# BMS_Slave_v2_1.net
KiCad netlist of a schematic drawn in EAGLE
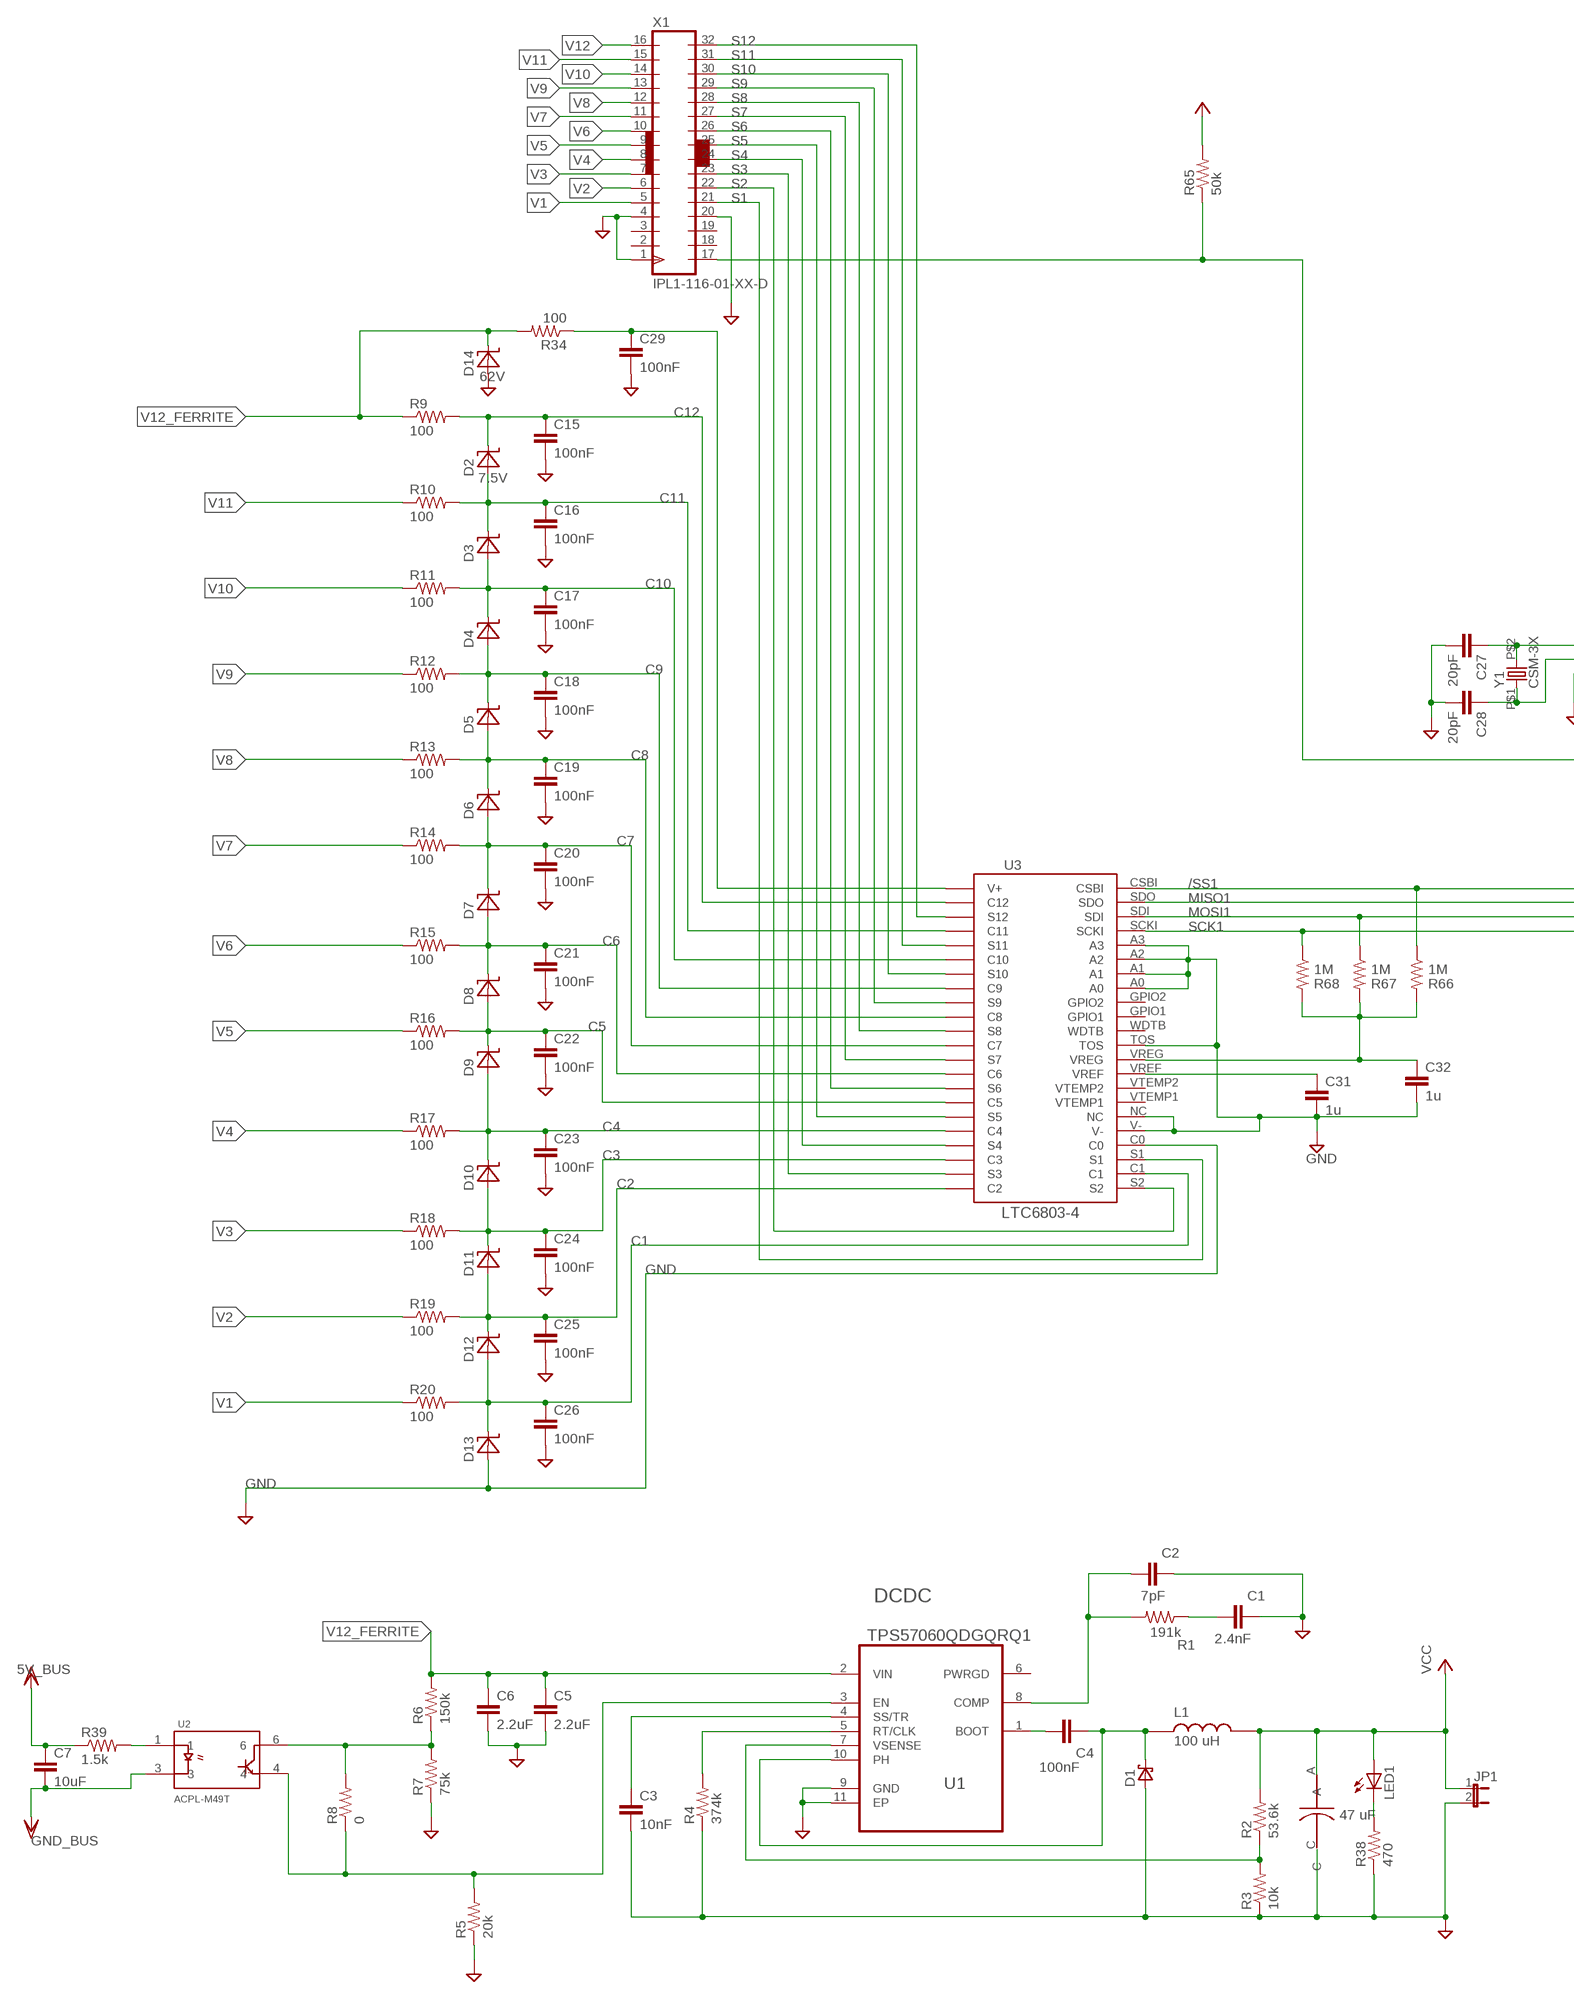
[diagram p0: schematic, sheet 1, part 1 of 2]
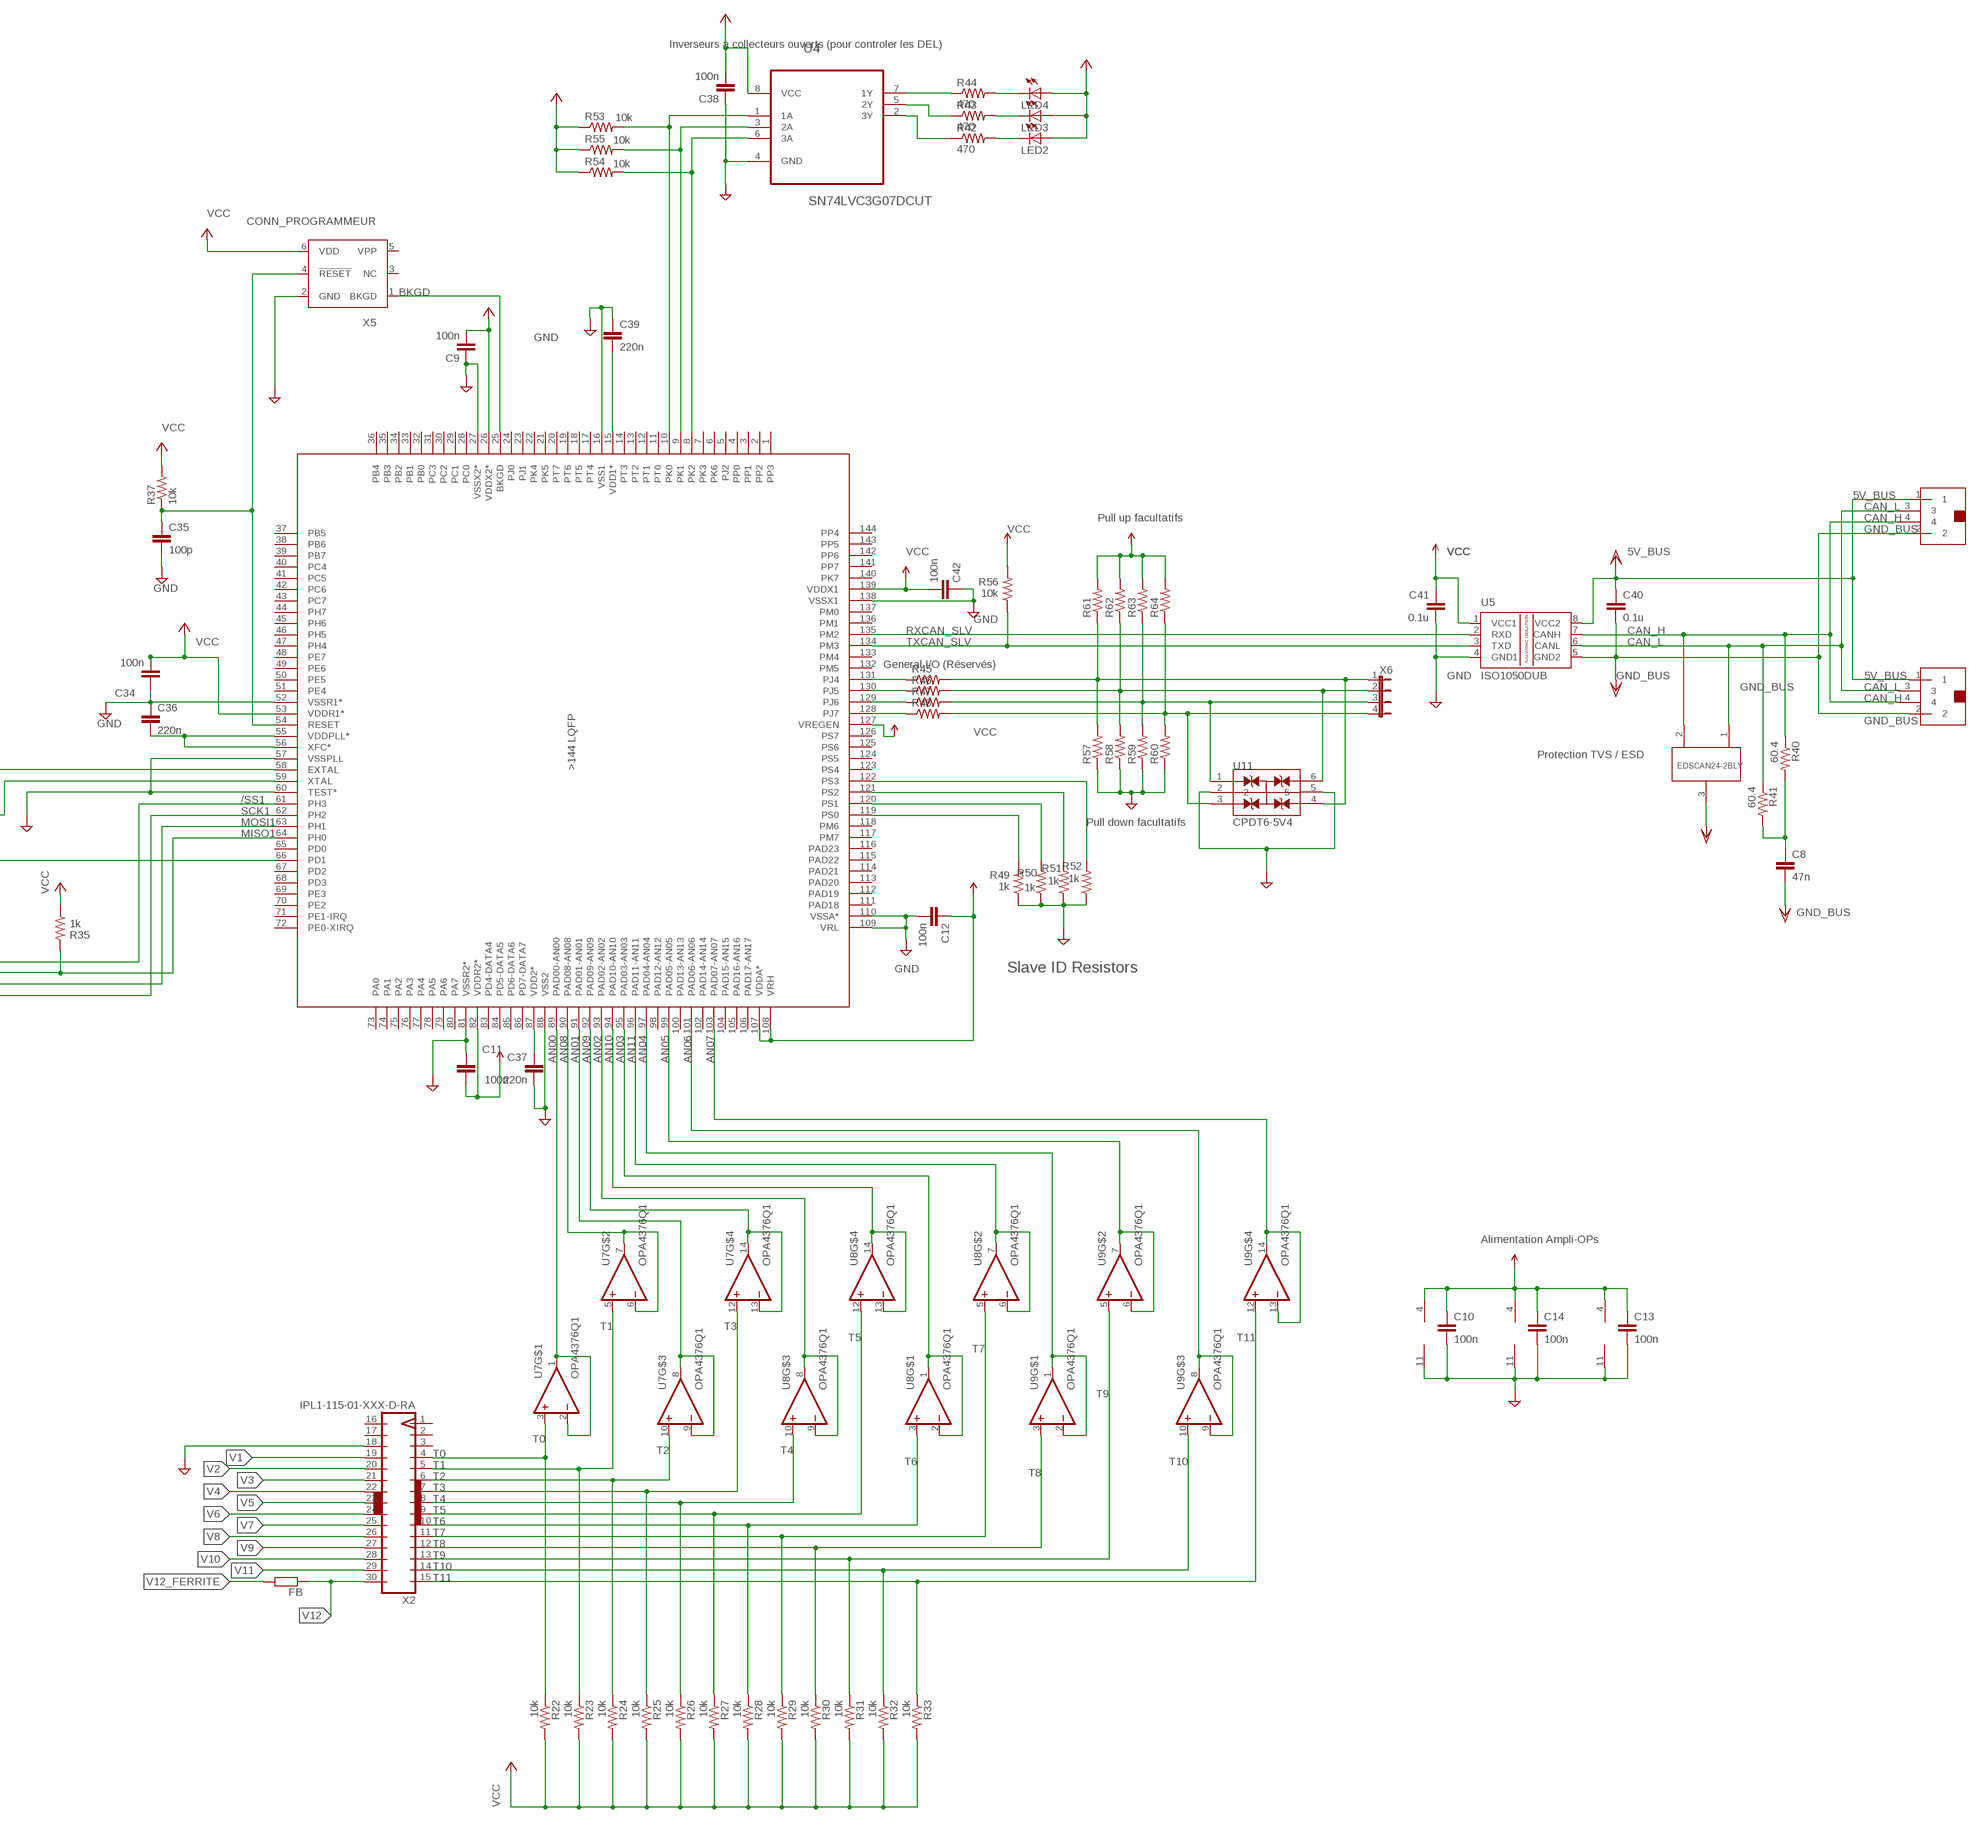
[diagram p1: schematic, sheet 1, part 2 of 2]

(export (version "E")
  (design (tool "Eeschema 10.0.6"))
  (components
    (comp (ref "C1")
      (value "2.4nF")
      (footprint "eagle-import:C0603")
      (libsource (lib "eagle-import") (part "CC0603"))
    )
    (comp (ref "C2")
      (value "7pF")
      (footprint "eagle-import:C0603")
      (libsource (lib "eagle-import") (part "CC0603"))
    )
    (comp (ref "C3")
      (value "10nF")
      (footprint "eagle-import:C0603")
      (libsource (lib "eagle-import") (part "CC0603"))
    )
    (comp (ref "C4")
      (value "100nF")
      (footprint "eagle-import:C0603")
      (libsource (lib "eagle-import") (part "CC0603"))
    )
    (comp (ref "C5")
      (value "2.2uF")
      (footprint "eagle-import:C3225")
      (libsource (lib "eagle-import") (part "resistor_C-EUC3225"))
    )
    (comp (ref "C6")
      (value "2.2uF")
      (footprint "eagle-import:C3225")
      (libsource (lib "eagle-import") (part "resistor_C-EUC3225"))
    )
    (comp (ref "C7")
      (value "10uF")
      (footprint "eagle-import:C0603")
      (libsource (lib "eagle-import") (part "CC0603"))
    )
    (comp (ref "C8")
      (value "47n")
      (footprint "eagle-import:C0603")
      (libsource (lib "eagle-import") (part "C-EUC0603"))
    )
    (comp (ref "C9")
      (value "100n")
      (footprint "eagle-import:C0603")
      (libsource (lib "eagle-import") (part "C-EUC0603"))
    )
    (comp (ref "C10")
      (value "100n")
      (footprint "eagle-import:C0603")
      (libsource (lib "eagle-import") (part "C-EUC0603"))
    )
    (comp (ref "C11")
      (value "100n")
      (footprint "eagle-import:C0603")
      (libsource (lib "eagle-import") (part "CC0603"))
    )
    (comp (ref "C12")
      (value "100n")
      (footprint "eagle-import:C0603")
      (libsource (lib "eagle-import") (part "C-EUC0603"))
    )
    (comp (ref "C13")
      (value "100n")
      (footprint "eagle-import:C0603")
      (libsource (lib "eagle-import") (part "C-EUC0603"))
    )
    (comp (ref "C14")
      (value "100n")
      (footprint "eagle-import:C0603")
      (libsource (lib "eagle-import") (part "C-EUC0603"))
    )
    (comp (ref "C15")
      (value "100nF")
      (footprint "eagle-import:C0603")
      (libsource (lib "eagle-import") (part "CC0603"))
    )
    (comp (ref "C16")
      (value "100nF")
      (footprint "eagle-import:C0603")
      (libsource (lib "eagle-import") (part "CC0603"))
    )
    (comp (ref "C17")
      (value "100nF")
      (footprint "eagle-import:C0603")
      (libsource (lib "eagle-import") (part "CC0603"))
    )
    (comp (ref "C18")
      (value "100nF")
      (footprint "eagle-import:C0603")
      (libsource (lib "eagle-import") (part "CC0603"))
    )
    (comp (ref "C19")
      (value "100nF")
      (footprint "eagle-import:C0603")
      (libsource (lib "eagle-import") (part "CC0603"))
    )
    (comp (ref "C20")
      (value "100nF")
      (footprint "eagle-import:C0603")
      (libsource (lib "eagle-import") (part "CC0603"))
    )
    (comp (ref "C21")
      (value "100nF")
      (footprint "eagle-import:C0603")
      (libsource (lib "eagle-import") (part "CC0603"))
    )
    (comp (ref "C22")
      (value "100nF")
      (footprint "eagle-import:C0603")
      (libsource (lib "eagle-import") (part "CC0603"))
    )
    (comp (ref "C23")
      (value "100nF")
      (footprint "eagle-import:C0603")
      (libsource (lib "eagle-import") (part "CC0603"))
    )
    (comp (ref "C24")
      (value "100nF")
      (footprint "eagle-import:C0603")
      (libsource (lib "eagle-import") (part "CC0603"))
    )
    (comp (ref "C25")
      (value "100nF")
      (footprint "eagle-import:C0603")
      (libsource (lib "eagle-import") (part "CC0603"))
    )
    (comp (ref "C26")
      (value "100nF")
      (footprint "eagle-import:C0603")
      (libsource (lib "eagle-import") (part "CC0603"))
    )
    (comp (ref "C27")
      (value "20pF")
      (footprint "eagle-import:C0603")
      (libsource (lib "eagle-import") (part "C-EUC0603"))
    )
    (comp (ref "C28")
      (value "20pF")
      (footprint "eagle-import:C0603")
      (libsource (lib "eagle-import") (part "C-EUC0603"))
    )
    (comp (ref "C29")
      (value "100nF")
      (footprint "eagle-import:C0603")
      (libsource (lib "eagle-import") (part "CC0603"))
    )
    (comp (ref "C31")
      (value "1u")
      (footprint "eagle-import:C0603")
      (libsource (lib "eagle-import") (part "CC0603"))
    )
    (comp (ref "C32")
      (value "1u")
      (footprint "eagle-import:C0603")
      (libsource (lib "eagle-import") (part "CC0603"))
    )
    (comp (ref "C34")
      (value "100n")
      (footprint "eagle-import:C0603")
      (libsource (lib "eagle-import") (part "CC0603"))
    )
    (comp (ref "C35")
      (value "100p")
      (footprint "eagle-import:C0603")
      (libsource (lib "eagle-import") (part "CC0603"))
    )
    (comp (ref "C36")
      (value "220n")
      (footprint "eagle-import:C0603")
      (libsource (lib "eagle-import") (part "CC0603"))
    )
    (comp (ref "C37")
      (value "220n")
      (footprint "eagle-import:C0603")
      (libsource (lib "eagle-import") (part "C-EUC0603"))
    )
    (comp (ref "C38")
      (value "100n")
      (footprint "eagle-import:C0603")
      (libsource (lib "eagle-import") (part "C-EUC0603"))
    )
    (comp (ref "C39")
      (value "220n")
      (footprint "eagle-import:C0603")
      (libsource (lib "eagle-import") (part "C-EUC0603"))
    )
    (comp (ref "C40")
      (value "0.1u")
      (footprint "eagle-import:C0603")
      (libsource (lib "eagle-import") (part "C-EUC0603"))
    )
    (comp (ref "C41")
      (value "0.1u")
      (footprint "eagle-import:C0603")
      (libsource (lib "eagle-import") (part "C-EUC0603"))
    )
    (comp (ref "C42")
      (value "100n")
      (footprint "eagle-import:C0603")
      (libsource (lib "eagle-import") (part "C-EUC0603"))
    )
    (comp (ref "C43")
      (value "47 uF")
      (footprint "eagle-import:APXE_CONDENSATEUR")
      (libsource (lib "eagle-import") (part "APXE_47_COND"))
    )
    (comp (ref "D1")
      (value "BYS12-90GENERIC")
      (footprint "eagle-import:DO214AC_ZENER")
      (libsource (lib "eagle-import") (part "BYS12-90GENERIC"))
    )
    (comp (ref "D2")
      (value "DIODE_ZENER")
      (footprint "eagle-import:SOD123")
      (libsource (lib "eagle-import") (part "DIODE_ZENER"))
    )
    (comp (ref "D3")
      (value "DIODE_ZENER")
      (footprint "eagle-import:SOD123")
      (libsource (lib "eagle-import") (part "DIODE_ZENER"))
    )
    (comp (ref "D4")
      (value "DIODE_ZENER")
      (footprint "eagle-import:SOD123")
      (libsource (lib "eagle-import") (part "DIODE_ZENER"))
    )
    (comp (ref "D5")
      (value "DIODE_ZENER")
      (footprint "eagle-import:SOD123")
      (libsource (lib "eagle-import") (part "DIODE_ZENER"))
    )
    (comp (ref "D6")
      (value "DIODE_ZENER")
      (footprint "eagle-import:SOD123")
      (libsource (lib "eagle-import") (part "DIODE_ZENER"))
    )
    (comp (ref "D7")
      (value "DIODE_ZENER")
      (footprint "eagle-import:SOD123")
      (libsource (lib "eagle-import") (part "DIODE_ZENER"))
    )
    (comp (ref "D8")
      (value "DIODE_ZENER")
      (footprint "eagle-import:SOD123")
      (libsource (lib "eagle-import") (part "DIODE_ZENER"))
    )
    (comp (ref "D9")
      (value "DIODE_ZENER")
      (footprint "eagle-import:SOD123")
      (libsource (lib "eagle-import") (part "DIODE_ZENER"))
    )
    (comp (ref "D10")
      (value "DIODE_ZENER")
      (footprint "eagle-import:SOD123")
      (libsource (lib "eagle-import") (part "DIODE_ZENER"))
    )
    (comp (ref "D11")
      (value "DIODE_ZENER")
      (footprint "eagle-import:SOD123")
      (libsource (lib "eagle-import") (part "DIODE_ZENER"))
    )
    (comp (ref "D12")
      (value "DIODE_ZENER")
      (footprint "eagle-import:SOD123")
      (libsource (lib "eagle-import") (part "DIODE_ZENER"))
    )
    (comp (ref "D13")
      (value "DIODE_ZENER")
      (footprint "eagle-import:SOD123")
      (libsource (lib "eagle-import") (part "DIODE_ZENER"))
    )
    (comp (ref "D14")
      (value "DIODE_ZENER")
      (footprint "eagle-import:SOD123")
      (libsource (lib "eagle-import") (part "DIODE_ZENER"))
    )
    (comp (ref "FB")
      (value "R-EU_R0805")
      (footprint "eagle-import:R0805")
      (libsource (lib "eagle-import") (part "R-EU_R0805"))
    )
    (comp (ref "JP1")
      (value "JP1E")
      (footprint "eagle-import:JP1")
      (libsource (lib "eagle-import") (part "JP1E"))
    )
    (comp (ref "L1")
      (value "100 uH")
      (footprint "eagle-import:VLP8040T-101M")
      (libsource (lib "eagle-import") (part "VLP8040T-101M"))
    )
    (comp (ref "LED1")
      (value "LED")
      (footprint "eagle-import:1206_LED")
      (libsource (lib "eagle-import") (part "LED"))
    )
    (comp (ref "LED2")
      (value "LED")
      (footprint "eagle-import:1206_LED")
      (libsource (lib "eagle-import") (part "ELE4000_BMS_LED"))
    )
    (comp (ref "LED3")
      (value "LED")
      (footprint "eagle-import:1206_LED")
      (libsource (lib "eagle-import") (part "ELE4000_BMS_LED"))
    )
    (comp (ref "LED4")
      (value "LED")
      (footprint "eagle-import:1206_LED")
      (libsource (lib "eagle-import") (part "ELE4000_BMS_LED"))
    )
    (comp (ref "R1")
      (value "191k")
      (footprint "eagle-import:R0603")
      (libsource (lib "eagle-import") (part "resistor_R-US_R0603"))
    )
    (comp (ref "R2")
      (value "53.6k")
      (footprint "eagle-import:R0603")
      (libsource (lib "eagle-import") (part "resistor_R-US_R0603"))
    )
    (comp (ref "R3")
      (value "10k")
      (footprint "eagle-import:R0603")
      (libsource (lib "eagle-import") (part "resistor_R-US_R0603"))
    )
    (comp (ref "R4")
      (value "374k")
      (footprint "eagle-import:R0603")
      (libsource (lib "eagle-import") (part "resistor_R-US_R0603"))
    )
    (comp (ref "R5")
      (value "20k")
      (footprint "eagle-import:R0603")
      (libsource (lib "eagle-import") (part "resistor_R-US_R0603"))
    )
    (comp (ref "R6")
      (value "150k")
      (footprint "eagle-import:R0603")
      (libsource (lib "eagle-import") (part "resistor_R-US_R0603"))
    )
    (comp (ref "R7")
      (value "75k")
      (footprint "eagle-import:R0603")
      (libsource (lib "eagle-import") (part "resistor_R-US_R0603"))
    )
    (comp (ref "R8")
      (value "0")
      (footprint "eagle-import:R0603")
      (libsource (lib "eagle-import") (part "resistor_R-US_R0603"))
    )
    (comp (ref "R9")
      (value "100")
      (footprint "eagle-import:R0603")
      (libsource (lib "eagle-import") (part "resistor_R-US_R0603"))
    )
    (comp (ref "R10")
      (value "100")
      (footprint "eagle-import:R0603")
      (libsource (lib "eagle-import") (part "resistor_R-US_R0603"))
    )
    (comp (ref "R11")
      (value "100")
      (footprint "eagle-import:R0603")
      (libsource (lib "eagle-import") (part "resistor_R-US_R0603"))
    )
    (comp (ref "R12")
      (value "100")
      (footprint "eagle-import:R0603")
      (libsource (lib "eagle-import") (part "resistor_R-US_R0603"))
    )
    (comp (ref "R13")
      (value "100")
      (footprint "eagle-import:R0603")
      (libsource (lib "eagle-import") (part "resistor_R-US_R0603"))
    )
    (comp (ref "R14")
      (value "100")
      (footprint "eagle-import:R0603")
      (libsource (lib "eagle-import") (part "resistor_R-US_R0603"))
    )
    (comp (ref "R15")
      (value "100")
      (footprint "eagle-import:R0603")
      (libsource (lib "eagle-import") (part "resistor_R-US_R0603"))
    )
    (comp (ref "R16")
      (value "100")
      (footprint "eagle-import:R0603")
      (libsource (lib "eagle-import") (part "resistor_R-US_R0603"))
    )
    (comp (ref "R17")
      (value "100")
      (footprint "eagle-import:R0603")
      (libsource (lib "eagle-import") (part "resistor_R-US_R0603"))
    )
    (comp (ref "R18")
      (value "100")
      (footprint "eagle-import:R0603")
      (libsource (lib "eagle-import") (part "resistor_R-US_R0603"))
    )
    (comp (ref "R19")
      (value "100")
      (footprint "eagle-import:R0603")
      (libsource (lib "eagle-import") (part "resistor_R-US_R0603"))
    )
    (comp (ref "R20")
      (value "100")
      (footprint "eagle-import:R0603")
      (libsource (lib "eagle-import") (part "resistor_R-US_R0603"))
    )
    (comp (ref "R22")
      (value "10k")
      (footprint "eagle-import:R0603")
      (libsource (lib "eagle-import") (part "R-US_R0603"))
    )
    (comp (ref "R23")
      (value "10k")
      (footprint "eagle-import:R0603")
      (libsource (lib "eagle-import") (part "R-US_R0603"))
    )
    (comp (ref "R24")
      (value "10k")
      (footprint "eagle-import:R0603")
      (libsource (lib "eagle-import") (part "R-US_R0603"))
    )
    (comp (ref "R25")
      (value "10k")
      (footprint "eagle-import:R0603")
      (libsource (lib "eagle-import") (part "R-US_R0603"))
    )
    (comp (ref "R26")
      (value "10k")
      (footprint "eagle-import:R0603")
      (libsource (lib "eagle-import") (part "R-US_R0603"))
    )
    (comp (ref "R27")
      (value "10k")
      (footprint "eagle-import:R0603")
      (libsource (lib "eagle-import") (part "R-US_R0603"))
    )
    (comp (ref "R28")
      (value "10k")
      (footprint "eagle-import:R0603")
      (libsource (lib "eagle-import") (part "R-US_R0603"))
    )
    (comp (ref "R29")
      (value "10k")
      (footprint "eagle-import:R0603")
      (libsource (lib "eagle-import") (part "R-US_R0603"))
    )
    (comp (ref "R30")
      (value "10k")
      (footprint "eagle-import:R0603")
      (libsource (lib "eagle-import") (part "R-US_R0603"))
    )
    (comp (ref "R31")
      (value "10k")
      (footprint "eagle-import:R0603")
      (libsource (lib "eagle-import") (part "R-US_R0603"))
    )
    (comp (ref "R32")
      (value "10k")
      (footprint "eagle-import:R0603")
      (libsource (lib "eagle-import") (part "R-US_R0603"))
    )
    (comp (ref "R33")
      (value "10k")
      (footprint "eagle-import:R0603")
      (libsource (lib "eagle-import") (part "R-US_R0603"))
    )
    (comp (ref "R34")
      (value "100")
      (footprint "eagle-import:R0603")
      (libsource (lib "eagle-import") (part "resistor_R-US_R0603"))
    )
    (comp (ref "R35")
      (value "1k")
      (footprint "eagle-import:R0603")
      (libsource (lib "eagle-import") (part "resistor_R-US_R0603"))
    )
    (comp (ref "R37")
      (value "10k")
      (footprint "eagle-import:R0603")
      (libsource (lib "eagle-import") (part "resistor_R-US_R0603"))
    )
    (comp (ref "R38")
      (value "470")
      (footprint "eagle-import:R0603")
      (libsource (lib "eagle-import") (part "R-US_R0603"))
    )
    (comp (ref "R39")
      (value "1.5k")
      (footprint "eagle-import:R0603")
      (libsource (lib "eagle-import") (part "resistor_R-US_R0603"))
    )
    (comp (ref "R40")
      (value "60.4")
      (footprint "eagle-import:R0603")
      (libsource (lib "eagle-import") (part "R-US_R0603"))
    )
    (comp (ref "R41")
      (value "60.4")
      (footprint "eagle-import:R0603")
      (libsource (lib "eagle-import") (part "R-US_R0603"))
    )
    (comp (ref "R42")
      (value "470")
      (footprint "eagle-import:R0603")
      (libsource (lib "eagle-import") (part "resistor_R-US_R0603"))
    )
    (comp (ref "R43")
      (value "470")
      (footprint "eagle-import:R0603")
      (libsource (lib "eagle-import") (part "resistor_R-US_R0603"))
    )
    (comp (ref "R44")
      (value "470")
      (footprint "eagle-import:R0603")
      (libsource (lib "eagle-import") (part "resistor_R-US_R0603"))
    )
    (comp (ref "R45")
      (value "R-US_R0603")
      (footprint "eagle-import:R0603")
      (libsource (lib "eagle-import") (part "R-US_R0603"))
    )
    (comp (ref "R46")
      (value "R-US_R0603")
      (footprint "eagle-import:R0603")
      (libsource (lib "eagle-import") (part "R-US_R0603"))
    )
    (comp (ref "R47")
      (value "R-US_R0603")
      (footprint "eagle-import:R0603")
      (libsource (lib "eagle-import") (part "R-US_R0603"))
    )
    (comp (ref "R48")
      (value "R-US_R0603")
      (footprint "eagle-import:R0603")
      (libsource (lib "eagle-import") (part "R-US_R0603"))
    )
    (comp (ref "R49")
      (value "1k")
      (footprint "eagle-import:R0603")
      (libsource (lib "eagle-import") (part "resistor_R-US_R0603"))
    )
    (comp (ref "R50")
      (value "1k")
      (footprint "eagle-import:R0603")
      (libsource (lib "eagle-import") (part "resistor_R-US_R0603"))
    )
    (comp (ref "R51")
      (value "1k")
      (footprint "eagle-import:R0603")
      (libsource (lib "eagle-import") (part "resistor_R-US_R0603"))
    )
    (comp (ref "R52")
      (value "1k")
      (footprint "eagle-import:R0603")
      (libsource (lib "eagle-import") (part "resistor_R-US_R0603"))
    )
    (comp (ref "R53")
      (value "10k")
      (footprint "eagle-import:R0603")
      (libsource (lib "eagle-import") (part "resistor_R-US_R0603"))
    )
    (comp (ref "R54")
      (value "10k")
      (footprint "eagle-import:R0603")
      (libsource (lib "eagle-import") (part "resistor_R-US_R0603"))
    )
    (comp (ref "R55")
      (value "10k")
      (footprint "eagle-import:R0603")
      (libsource (lib "eagle-import") (part "resistor_R-US_R0603"))
    )
    (comp (ref "R56")
      (value "10k")
      (footprint "eagle-import:R0603")
      (libsource (lib "eagle-import") (part "resistor_R-US_R0603"))
    )
    (comp (ref "R57")
      (value "R-US_R0603")
      (footprint "eagle-import:R0603")
      (libsource (lib "eagle-import") (part "R-US_R0603"))
    )
    (comp (ref "R58")
      (value "R-US_R0603")
      (footprint "eagle-import:R0603")
      (libsource (lib "eagle-import") (part "R-US_R0603"))
    )
    (comp (ref "R59")
      (value "R-US_R0603")
      (footprint "eagle-import:R0603")
      (libsource (lib "eagle-import") (part "R-US_R0603"))
    )
    (comp (ref "R60")
      (value "R-US_R0603")
      (footprint "eagle-import:R0603")
      (libsource (lib "eagle-import") (part "R-US_R0603"))
    )
    (comp (ref "R61")
      (value "R-US_R0603")
      (footprint "eagle-import:R0603")
      (libsource (lib "eagle-import") (part "R-US_R0603"))
    )
    (comp (ref "R62")
      (value "R-US_R0603")
      (footprint "eagle-import:R0603")
      (libsource (lib "eagle-import") (part "R-US_R0603"))
    )
    (comp (ref "R63")
      (value "R-US_R0603")
      (footprint "eagle-import:R0603")
      (libsource (lib "eagle-import") (part "R-US_R0603"))
    )
    (comp (ref "R64")
      (value "R-US_R0603")
      (footprint "eagle-import:R0603")
      (libsource (lib "eagle-import") (part "R-US_R0603"))
    )
    (comp (ref "R65")
      (value "50k")
      (footprint "eagle-import:R0603")
      (libsource (lib "eagle-import") (part "resistor_R-US_R0603"))
    )
    (comp (ref "R66")
      (value "1M")
      (footprint "eagle-import:R0603")
      (libsource (lib "eagle-import") (part "resistor_R-US_R0603"))
    )
    (comp (ref "R67")
      (value "1M")
      (footprint "eagle-import:R0603")
      (libsource (lib "eagle-import") (part "resistor_R-US_R0603"))
    )
    (comp (ref "R68")
      (value "1M")
      (footprint "eagle-import:R0603")
      (libsource (lib "eagle-import") (part "resistor_R-US_R0603"))
    )
    (comp (ref "U1")
      (value "TPS57060QDGQRQ1")
      (footprint "eagle-import:SOP50P490X110-11N")
      (fields (field (name "MPN") "TPS54060QDGQRQ1"))
      (libsource (lib "eagle-import") (part "TPS54060QDGQRQ1"))
    )
    (comp (ref "U2")
      (value "ACPL-M49T")
      (footprint "eagle-import:SO5")
      (libsource (lib "eagle-import") (part "ACPL-M49T"))
    )
    (comp (ref "U3")
      (value "LTC6803-4")
      (footprint "eagle-import:LTC6803-4")
      (libsource (lib "eagle-import") (part "LTC6803-4"))
    )
    (comp (ref "U4")
      (value "SN74LVC3G07DCUT")
      (footprint "eagle-import:SOP50P310X90-8N")
      (libsource (lib "eagle-import") (part "SN74LVC3G07DCUT"))
    )
    (comp (ref "U5")
      (value "ISO1050DUB")
      (footprint "eagle-import:DUB-R-PDSO-G8")
      (fields (field (name "MPN") "ISO1050DUBR"))
      (libsource (lib "eagle-import") (part "ISO1050DUB"))
    )
    (comp (ref "U6")
      (value "MC9S12XD-144")
      (footprint "eagle-import:SQFP-S-20X20-144")
      (fields (field (name "MPN") "LFDAS12XFLT"))
      (libsource (lib "eagle-import") (part "MC9S12XD-144"))
    )
    (comp (ref "U7")
      (value "OPA4376Q1")
      (footprint "eagle-import:TSSOP-14")
      (libsource (lib "eagle-import") (part "OPA4376Q1"))
    )
    (comp (ref "U8")
      (value "OPA4376Q1")
      (footprint "eagle-import:TSSOP-14")
      (libsource (lib "eagle-import") (part "OPA4376Q1"))
    )
    (comp (ref "U9")
      (value "OPA4376Q1")
      (footprint "eagle-import:TSSOP-14")
      (libsource (lib "eagle-import") (part "OPA4376Q1"))
    )
    (comp (ref "U10")
      (value "EDSCAN24-2BLY")
      (footprint "eagle-import:SOT23-3")
      (libsource (lib "eagle-import") (part "EDSCAN24-2BLY"))
    )
    (comp (ref "U11")
      (value "CPDT6-5V4")
      (footprint "eagle-import:SOT23-6")
      (libsource (lib "eagle-import") (part "CPDT6-5V4"))
    )
    (comp (ref "X1")
      (value "IPL1-116-01-XX-D")
      (footprint "eagle-import:IPL1-116-01-XX-D")
      (libsource (lib "eagle-import") (part "IPL1-116-01-XX-D"))
    )
    (comp (ref "X2")
      (value "IPL1-115-01-XXX-D-RA")
      (footprint "eagle-import:IPL1-115-01-XXX-D-RA")
      (libsource (lib "eagle-import") (part "IPL1-115-01-XXX-D-RA"))
    )
    (comp (ref "X3")
      (value "IPL1-102-01-XXX-D-RA")
      (footprint "eagle-import:IPL1-102-01-XXX-D-RA")
      (libsource (lib "eagle-import") (part "IPL1-102-01-XXX-D-RA"))
    )
    (comp (ref "X4")
      (value "IPL1-102-01-XXX-D-RA")
      (footprint "eagle-import:IPL1-102-01-XXX-D-RA")
      (libsource (lib "eagle-import") (part "IPL1-102-01-XXX-D-RA"))
    )
    (comp (ref "X5")
      (value "CONN_PROGRAMMEUR")
      (footprint "eagle-import:CONNECTEUR_PROGRAMMEUR")
      (libsource (lib "eagle-import") (part "CONN_PROGRAMMEUR"))
    )
    (comp (ref "X6")
      (value "JP4E")
      (footprint "eagle-import:JP4")
      (libsource (lib "eagle-import") (part "JP4E"))
    )
    (comp (ref "Y1")
      (value "CSM-3X")
      (footprint "eagle-import:CSM-3X")
      (libsource (lib "eagle-import") (part "CSM-3X"))
    )
  )
  (nets
    (net (code "1") (name "/AN00") (class "Default")
      (node (ref "U6") (pin "89") (pinfunction "PAD00-AN00_89") (pintype "bidirectional"))
      (node (ref "U7") (pin "1") (pinfunction "OUT_1") (pintype "output"))
      (node (ref "U7") (pin "2") (pinfunction "-IN_2") (pintype "input"))
    )
    (net (code "2") (name "/AN01") (class "Default")
      (node (ref "U6") (pin "91") (pinfunction "PAD01-AN01_91") (pintype "bidirectional"))
      (node (ref "U7") (pin "8") (pinfunction "OUT_8") (pintype "output"))
      (node (ref "U7") (pin "9") (pinfunction "-IN_9") (pintype "input"))
    )
    (net (code "3") (name "/AN02") (class "Default")
      (node (ref "U6") (pin "93") (pinfunction "PAD02-AN02_93") (pintype "bidirectional"))
      (node (ref "U8") (pin "8") (pinfunction "OUT_8") (pintype "output"))
      (node (ref "U8") (pin "9") (pinfunction "-IN_9") (pintype "input"))
    )
    (net (code "4") (name "/AN03") (class "Default")
      (node (ref "U6") (pin "95") (pinfunction "PAD03-AN03_95") (pintype "bidirectional"))
      (node (ref "U8") (pin "1") (pinfunction "OUT_1") (pintype "output"))
      (node (ref "U8") (pin "2") (pinfunction "-IN_2") (pintype "input"))
    )
    (net (code "5") (name "/AN04") (class "Default")
      (node (ref "U6") (pin "97") (pinfunction "PAD04-AN04_97") (pintype "bidirectional"))
      (node (ref "U9") (pin "1") (pinfunction "OUT_1") (pintype "output"))
      (node (ref "U9") (pin "2") (pinfunction "-IN_2") (pintype "input"))
    )
    (net (code "6") (name "/AN05") (class "Default")
      (node (ref "U6") (pin "99") (pinfunction "PAD05-AN05_99") (pintype "bidirectional"))
      (node (ref "U9") (pin "6") (pinfunction "-IN_6") (pintype "input"))
      (node (ref "U9") (pin "7") (pinfunction "OUT_7") (pintype "output"))
    )
    (net (code "7") (name "/AN06") (class "Default")
      (node (ref "U6") (pin "101") (pinfunction "PAD06-AN06_101") (pintype "bidirectional"))
      (node (ref "U9") (pin "8") (pinfunction "OUT_8") (pintype "output"))
      (node (ref "U9") (pin "9") (pinfunction "-IN_9") (pintype "input"))
    )
    (net (code "8") (name "/AN07") (class "Default")
      (node (ref "U6") (pin "103") (pinfunction "PAD07-AN07_103") (pintype "bidirectional"))
      (node (ref "U9") (pin "13") (pinfunction "-IN_13") (pintype "input"))
      (node (ref "U9") (pin "14") (pinfunction "OUT_14") (pintype "output"))
    )
    (net (code "9") (name "/AN08") (class "Default")
      (node (ref "U6") (pin "90") (pinfunction "PAD08-AN08_90") (pintype "bidirectional"))
      (node (ref "U7") (pin "6") (pinfunction "-IN_6") (pintype "input"))
      (node (ref "U7") (pin "7") (pinfunction "OUT_7") (pintype "output"))
    )
    (net (code "10") (name "/AN09") (class "Default")
      (node (ref "U6") (pin "92") (pinfunction "PAD09-AN09_92") (pintype "bidirectional"))
      (node (ref "U7") (pin "13") (pinfunction "-IN_13") (pintype "input"))
      (node (ref "U7") (pin "14") (pinfunction "OUT_14") (pintype "output"))
    )
    (net (code "11") (name "/AN10") (class "Default")
      (node (ref "U6") (pin "94") (pinfunction "PAD10-AN10_94") (pintype "bidirectional"))
      (node (ref "U8") (pin "13") (pinfunction "-IN_13") (pintype "input"))
      (node (ref "U8") (pin "14") (pinfunction "OUT_14") (pintype "output"))
    )
    (net (code "12") (name "/AN11") (class "Default")
      (node (ref "U6") (pin "96") (pinfunction "PAD11-AN11_96") (pintype "bidirectional"))
      (node (ref "U8") (pin "6") (pinfunction "-IN_6") (pintype "input"))
      (node (ref "U8") (pin "7") (pinfunction "OUT_7") (pintype "output"))
    )
    (net (code "13") (name "/BKGD") (class "Default")
      (node (ref "U6") (pin "25") (pinfunction "BKGD_25") (pintype "bidirectional"))
      (node (ref "X5") (pin "1") (pinfunction "BKGD_1") (pintype "bidirectional"))
    )
    (net (code "14") (name "/C1") (class "Default")
      (node (ref "C26") (pin "1") (pinfunction "1_1") (pintype "passive"))
      (node (ref "D12") (pin "A") (pinfunction "A_A") (pintype "passive"))
      (node (ref "D13") (pin "C") (pinfunction "C_C") (pintype "passive"))
      (node (ref "R20") (pin "2") (pinfunction "2_2") (pintype "passive"))
      (node (ref "U3") (pin "C1") (pinfunction "C1_C1") (pintype "bidirectional"))
    )
    (net (code "15") (name "/C2") (class "Default")
      (node (ref "C25") (pin "1") (pinfunction "1_1") (pintype "passive"))
      (node (ref "D11") (pin "A") (pinfunction "A_A") (pintype "passive"))
      (node (ref "D12") (pin "C") (pinfunction "C_C") (pintype "passive"))
      (node (ref "R19") (pin "2") (pinfunction "2_2") (pintype "passive"))
      (node (ref "U3") (pin "C2") (pinfunction "C2_C2") (pintype "bidirectional"))
    )
    (net (code "16") (name "/C3") (class "Default")
      (node (ref "C24") (pin "1") (pinfunction "1_1") (pintype "passive"))
      (node (ref "D10") (pin "A") (pinfunction "A_A") (pintype "passive"))
      (node (ref "D11") (pin "C") (pinfunction "C_C") (pintype "passive"))
      (node (ref "R18") (pin "2") (pinfunction "2_2") (pintype "passive"))
      (node (ref "U3") (pin "C3") (pinfunction "C3_C3") (pintype "bidirectional"))
    )
    (net (code "17") (name "/C4") (class "Default")
      (node (ref "C23") (pin "1") (pinfunction "1_1") (pintype "passive"))
      (node (ref "D10") (pin "C") (pinfunction "C_C") (pintype "passive"))
      (node (ref "D9") (pin "A") (pinfunction "A_A") (pintype "passive"))
      (node (ref "R17") (pin "2") (pinfunction "2_2") (pintype "passive"))
      (node (ref "U3") (pin "C4") (pinfunction "C4_C4") (pintype "bidirectional"))
    )
    (net (code "18") (name "/C5") (class "Default")
      (node (ref "C22") (pin "1") (pinfunction "1_1") (pintype "passive"))
      (node (ref "D8") (pin "A") (pinfunction "A_A") (pintype "passive"))
      (node (ref "D9") (pin "C") (pinfunction "C_C") (pintype "passive"))
      (node (ref "R16") (pin "2") (pinfunction "2_2") (pintype "passive"))
      (node (ref "U3") (pin "C5") (pinfunction "C5_C5") (pintype "bidirectional"))
    )
    (net (code "19") (name "/C6") (class "Default")
      (node (ref "C21") (pin "1") (pinfunction "1_1") (pintype "passive"))
      (node (ref "D7") (pin "A") (pinfunction "A_A") (pintype "passive"))
      (node (ref "D8") (pin "C") (pinfunction "C_C") (pintype "passive"))
      (node (ref "R15") (pin "2") (pinfunction "2_2") (pintype "passive"))
      (node (ref "U3") (pin "C6") (pinfunction "C6_C6") (pintype "bidirectional"))
    )
    (net (code "20") (name "/C7") (class "Default")
      (node (ref "C20") (pin "1") (pinfunction "1_1") (pintype "passive"))
      (node (ref "D6") (pin "A") (pinfunction "A_A") (pintype "passive"))
      (node (ref "D7") (pin "C") (pinfunction "C_C") (pintype "passive"))
      (node (ref "R14") (pin "2") (pinfunction "2_2") (pintype "passive"))
      (node (ref "U3") (pin "C7") (pinfunction "C7_C7") (pintype "bidirectional"))
    )
    (net (code "21") (name "/C8") (class "Default")
      (node (ref "C19") (pin "1") (pinfunction "1_1") (pintype "passive"))
      (node (ref "D5") (pin "A") (pinfunction "A_A") (pintype "passive"))
      (node (ref "D6") (pin "C") (pinfunction "C_C") (pintype "passive"))
      (node (ref "R13") (pin "2") (pinfunction "2_2") (pintype "passive"))
      (node (ref "U3") (pin "C8") (pinfunction "C8_C8") (pintype "bidirectional"))
    )
    (net (code "22") (name "/C9") (class "Default")
      (node (ref "C18") (pin "1") (pinfunction "1_1") (pintype "passive"))
      (node (ref "D4") (pin "A") (pinfunction "A_A") (pintype "passive"))
      (node (ref "D5") (pin "C") (pinfunction "C_C") (pintype "passive"))
      (node (ref "R12") (pin "2") (pinfunction "2_2") (pintype "passive"))
      (node (ref "U3") (pin "C9") (pinfunction "C9_C9") (pintype "bidirectional"))
    )
    (net (code "23") (name "/C10") (class "Default")
      (node (ref "C17") (pin "1") (pinfunction "1_1") (pintype "passive"))
      (node (ref "D3") (pin "A") (pinfunction "A_A") (pintype "passive"))
      (node (ref "D4") (pin "C") (pinfunction "C_C") (pintype "passive"))
      (node (ref "R11") (pin "2") (pinfunction "2_2") (pintype "passive"))
      (node (ref "U3") (pin "C10") (pinfunction "C10_C10") (pintype "bidirectional"))
    )
    (net (code "24") (name "/C11") (class "Default")
      (node (ref "C16") (pin "1") (pinfunction "1_1") (pintype "passive"))
      (node (ref "D2") (pin "A") (pinfunction "A_A") (pintype "passive"))
      (node (ref "D3") (pin "C") (pinfunction "C_C") (pintype "passive"))
      (node (ref "R10") (pin "2") (pinfunction "2_2") (pintype "passive"))
      (node (ref "U3") (pin "C11") (pinfunction "C11_C11") (pintype "bidirectional"))
    )
    (net (code "25") (name "/C12") (class "Default")
      (node (ref "C15") (pin "1") (pinfunction "1_1") (pintype "passive"))
      (node (ref "D2") (pin "C") (pinfunction "C_C") (pintype "passive"))
      (node (ref "R9") (pin "2") (pinfunction "2_2") (pintype "passive"))
      (node (ref "U3") (pin "C12") (pinfunction "C12_C12") (pintype "bidirectional"))
    )
    (net (code "26") (name "/CAN_H") (class "Default")
      (node (ref "R40") (pin "1") (pinfunction "1_1") (pintype "passive"))
      (node (ref "U10") (pin "2") (pinfunction "2_2") (pintype "bidirectional"))
      (node (ref "U5") (pin "7") (pinfunction "CANH_7") (pintype "input"))
      (node (ref "X3") (pin "4") (pinfunction "4_4") (pintype "bidirectional"))
      (node (ref "X4") (pin "4") (pinfunction "4_4") (pintype "bidirectional"))
    )
    (net (code "27") (name "/CAN_L") (class "Default")
      (node (ref "R41") (pin "1") (pinfunction "1_1") (pintype "passive"))
      (node (ref "U10") (pin "1") (pinfunction "1_1") (pintype "bidirectional"))
      (node (ref "U5") (pin "6") (pinfunction "CANL_6") (pintype "input"))
      (node (ref "X3") (pin "3") (pinfunction "3_3") (pintype "bidirectional"))
      (node (ref "X4") (pin "3") (pinfunction "3_3") (pintype "bidirectional"))
    )
    (net (code "28") (name "/MISO1") (class "Default")
      (node (ref "R35") (pin "2") (pinfunction "2_2") (pintype "passive"))
      (node (ref "U3") (pin "SDO") (pinfunction "SDO_SDO") (pintype "bidirectional"))
      (node (ref "U6") (pin "64") (pinfunction "PH0_64") (pintype "bidirectional"))
    )
    (net (code "29") (name "/MOSI1") (class "Default")
      (node (ref "R67") (pin "1") (pinfunction "1_1") (pintype "passive"))
      (node (ref "U3") (pin "SDI") (pinfunction "SDI_SDI") (pintype "bidirectional"))
      (node (ref "U6") (pin "63") (pinfunction "PH1_63") (pintype "bidirectional"))
    )
    (net (code "30") (name "/RXCAN_SLV") (class "Default")
      (node (ref "U5") (pin "2") (pinfunction "RXD_2") (pintype "input"))
      (node (ref "U6") (pin "135") (pinfunction "PM2_135") (pintype "bidirectional"))
    )
    (net (code "31") (name "/S1") (class "Default")
      (node (ref "U3") (pin "S1") (pinfunction "S1_S1") (pintype "bidirectional"))
      (node (ref "X1") (pin "21") (pinfunction "21_21") (pintype "bidirectional"))
    )
    (net (code "32") (name "/S2") (class "Default")
      (node (ref "U3") (pin "S2") (pinfunction "S2_S2") (pintype "bidirectional"))
      (node (ref "X1") (pin "22") (pinfunction "22_22") (pintype "bidirectional"))
    )
    (net (code "33") (name "/S3") (class "Default")
      (node (ref "U3") (pin "S3") (pinfunction "S3_S3") (pintype "bidirectional"))
      (node (ref "X1") (pin "23") (pinfunction "23_23") (pintype "bidirectional"))
    )
    (net (code "34") (name "/S4") (class "Default")
      (node (ref "U3") (pin "S4") (pinfunction "S4_S4") (pintype "bidirectional"))
      (node (ref "X1") (pin "24") (pinfunction "24_24") (pintype "bidirectional"))
    )
    (net (code "35") (name "/S5") (class "Default")
      (node (ref "U3") (pin "S5") (pinfunction "S5_S5") (pintype "bidirectional"))
      (node (ref "X1") (pin "25") (pinfunction "25_25") (pintype "bidirectional"))
    )
    (net (code "36") (name "/S6") (class "Default")
      (node (ref "U3") (pin "S6") (pinfunction "S6_S6") (pintype "bidirectional"))
      (node (ref "X1") (pin "26") (pinfunction "26_26") (pintype "bidirectional"))
    )
    (net (code "37") (name "/S7") (class "Default")
      (node (ref "U3") (pin "S7") (pinfunction "S7_S7") (pintype "bidirectional"))
      (node (ref "X1") (pin "27") (pinfunction "27_27") (pintype "bidirectional"))
    )
    (net (code "38") (name "/S8") (class "Default")
      (node (ref "U3") (pin "S8") (pinfunction "S8_S8") (pintype "bidirectional"))
      (node (ref "X1") (pin "28") (pinfunction "28_28") (pintype "bidirectional"))
    )
    (net (code "39") (name "/S9") (class "Default")
      (node (ref "U3") (pin "S9") (pinfunction "S9_S9") (pintype "bidirectional"))
      (node (ref "X1") (pin "29") (pinfunction "29_29") (pintype "bidirectional"))
    )
    (net (code "40") (name "/S10") (class "Default")
      (node (ref "U3") (pin "S10") (pinfunction "S10_S10") (pintype "bidirectional"))
      (node (ref "X1") (pin "30") (pinfunction "30_30") (pintype "bidirectional"))
    )
    (net (code "41") (name "/S11") (class "Default")
      (node (ref "U3") (pin "S11") (pinfunction "S11_S11") (pintype "bidirectional"))
      (node (ref "X1") (pin "31") (pinfunction "31_31") (pintype "bidirectional"))
    )
    (net (code "42") (name "/S12") (class "Default")
      (node (ref "U3") (pin "S12") (pinfunction "S12_S12") (pintype "bidirectional"))
      (node (ref "X1") (pin "32") (pinfunction "32_32") (pintype "bidirectional"))
    )
    (net (code "43") (name "/SCK1") (class "Default")
      (node (ref "R68") (pin "1") (pinfunction "1_1") (pintype "passive"))
      (node (ref "U3") (pin "SCKI") (pinfunction "SCKI_SCKI") (pintype "bidirectional"))
      (node (ref "U6") (pin "62") (pinfunction "PH2_62") (pintype "bidirectional"))
    )
    (net (code "44") (name "/T0") (class "Default")
      (node (ref "R22") (pin "1") (pinfunction "1_1") (pintype "passive"))
      (node (ref "U7") (pin "3") (pinfunction "+IN_3") (pintype "input"))
      (node (ref "X2") (pin "4") (pinfunction "4_4") (pintype "bidirectional"))
    )
    (net (code "45") (name "/T1") (class "Default")
      (node (ref "R23") (pin "1") (pinfunction "1_1") (pintype "passive"))
      (node (ref "U7") (pin "5") (pinfunction "+IN_5") (pintype "input"))
      (node (ref "X2") (pin "5") (pinfunction "5_5") (pintype "bidirectional"))
    )
    (net (code "46") (name "/T2") (class "Default")
      (node (ref "R24") (pin "1") (pinfunction "1_1") (pintype "passive"))
      (node (ref "U7") (pin "10") (pinfunction "+IN_10") (pintype "input"))
      (node (ref "X2") (pin "6") (pinfunction "6_6") (pintype "bidirectional"))
    )
    (net (code "47") (name "/T3") (class "Default")
      (node (ref "R25") (pin "1") (pinfunction "1_1") (pintype "passive"))
      (node (ref "U7") (pin "12") (pinfunction "+IN_12") (pintype "input"))
      (node (ref "X2") (pin "7") (pinfunction "7_7") (pintype "bidirectional"))
    )
    (net (code "48") (name "/T4") (class "Default")
      (node (ref "R26") (pin "1") (pinfunction "1_1") (pintype "passive"))
      (node (ref "U8") (pin "10") (pinfunction "+IN_10") (pintype "input"))
      (node (ref "X2") (pin "8") (pinfunction "8_8") (pintype "bidirectional"))
    )
    (net (code "49") (name "/T5") (class "Default")
      (node (ref "R27") (pin "1") (pinfunction "1_1") (pintype "passive"))
      (node (ref "U8") (pin "12") (pinfunction "+IN_12") (pintype "input"))
      (node (ref "X2") (pin "9") (pinfunction "9_9") (pintype "bidirectional"))
    )
    (net (code "50") (name "/T6") (class "Default")
      (node (ref "R28") (pin "1") (pinfunction "1_1") (pintype "passive"))
      (node (ref "U8") (pin "3") (pinfunction "+IN_3") (pintype "input"))
      (node (ref "X2") (pin "10") (pinfunction "10_10") (pintype "bidirectional"))
    )
    (net (code "51") (name "/T7") (class "Default")
      (node (ref "R29") (pin "1") (pinfunction "1_1") (pintype "passive"))
      (node (ref "U8") (pin "5") (pinfunction "+IN_5") (pintype "input"))
      (node (ref "X2") (pin "11") (pinfunction "11_11") (pintype "bidirectional"))
    )
    (net (code "52") (name "/T8") (class "Default")
      (node (ref "R30") (pin "1") (pinfunction "1_1") (pintype "passive"))
      (node (ref "U9") (pin "3") (pinfunction "+IN_3") (pintype "input"))
      (node (ref "X2") (pin "12") (pinfunction "12_12") (pintype "bidirectional"))
    )
    (net (code "53") (name "/T9") (class "Default")
      (node (ref "R31") (pin "1") (pinfunction "1_1") (pintype "passive"))
      (node (ref "U9") (pin "5") (pinfunction "+IN_5") (pintype "input"))
      (node (ref "X2") (pin "13") (pinfunction "13_13") (pintype "bidirectional"))
    )
    (net (code "54") (name "/T10") (class "Default")
      (node (ref "R32") (pin "1") (pinfunction "1_1") (pintype "passive"))
      (node (ref "U9") (pin "10") (pinfunction "+IN_10") (pintype "input"))
      (node (ref "X2") (pin "14") (pinfunction "14_14") (pintype "bidirectional"))
    )
    (net (code "55") (name "/T11") (class "Default")
      (node (ref "R33") (pin "1") (pinfunction "1_1") (pintype "passive"))
      (node (ref "U9") (pin "12") (pinfunction "+IN_12") (pintype "input"))
      (node (ref "X2") (pin "15") (pinfunction "15_15") (pintype "bidirectional"))
    )
    (net (code "56") (name "/TXCAN_SLV") (class "Default")
      (node (ref "R56") (pin "1") (pinfunction "1_1") (pintype "passive"))
      (node (ref "U5") (pin "3") (pinfunction "TXD_3") (pintype "input"))
      (node (ref "U6") (pin "134") (pinfunction "PM3_134") (pintype "bidirectional"))
    )
    (net (code "57") (name "/{slash}SS1") (class "Default")
      (node (ref "R66") (pin "1") (pinfunction "1_1") (pintype "passive"))
      (node (ref "U3") (pin "CSBI") (pinfunction "CSBI_CSBI") (pintype "bidirectional"))
      (node (ref "U6") (pin "61") (pinfunction "PH3_61") (pintype "bidirectional"))
    )
    (net (code "58") (name "5V_BUS") (class "Default")
      (node (ref "C40") (pin "1") (pinfunction "1_1") (pintype "passive"))
      (node (ref "C7") (pin "1") (pinfunction "1_1") (pintype "passive"))
      (node (ref "R39") (pin "1") (pinfunction "1_1") (pintype "passive"))
      (node (ref "U5") (pin "8") (pinfunction "VCC2_8") (pintype "input"))
      (node (ref "X3") (pin "1") (pinfunction "1_1") (pintype "bidirectional"))
      (node (ref "X4") (pin "1") (pinfunction "1_1") (pintype "bidirectional"))
    )
    (net (code "59") (name "GND") (class "Default")
      (node (ref "C1") (pin "2") (pinfunction "2_2") (pintype "passive"))
      (node (ref "C10") (pin "2") (pinfunction "2_2") (pintype "passive"))
      (node (ref "C11") (pin "1") (pinfunction "1_1") (pintype "passive"))
      (node (ref "C12") (pin "2") (pinfunction "2_2") (pintype "passive"))
      (node (ref "C13") (pin "2") (pinfunction "2_2") (pintype "passive"))
      (node (ref "C14") (pin "2") (pinfunction "2_2") (pintype "passive"))
      (node (ref "C15") (pin "2") (pinfunction "2_2") (pintype "passive"))
      (node (ref "C16") (pin "2") (pinfunction "2_2") (pintype "passive"))
      (node (ref "C17") (pin "2") (pinfunction "2_2") (pintype "passive"))
      (node (ref "C18") (pin "2") (pinfunction "2_2") (pintype "passive"))
      (node (ref "C19") (pin "2") (pinfunction "2_2") (pintype "passive"))
      (node (ref "C2") (pin "2") (pinfunction "2_2") (pintype "passive"))
      (node (ref "C20") (pin "2") (pinfunction "2_2") (pintype "passive"))
      (node (ref "C21") (pin "2") (pinfunction "2_2") (pintype "passive"))
      (node (ref "C22") (pin "2") (pinfunction "2_2") (pintype "passive"))
      (node (ref "C23") (pin "2") (pinfunction "2_2") (pintype "passive"))
      (node (ref "C24") (pin "2") (pinfunction "2_2") (pintype "passive"))
      (node (ref "C25") (pin "2") (pinfunction "2_2") (pintype "passive"))
      (node (ref "C26") (pin "2") (pinfunction "2_2") (pintype "passive"))
      (node (ref "C27") (pin "2") (pinfunction "2_2") (pintype "passive"))
      (node (ref "C28") (pin "2") (pinfunction "2_2") (pintype "passive"))
      (node (ref "C29") (pin "2") (pinfunction "2_2") (pintype "passive"))
      (node (ref "C3") (pin "2") (pinfunction "2_2") (pintype "passive"))
      (node (ref "C31") (pin "2") (pinfunction "2_2") (pintype "passive"))
      (node (ref "C32") (pin "2") (pinfunction "2_2") (pintype "passive"))
      (node (ref "C34") (pin "1") (pinfunction "1_1") (pintype "passive"))
      (node (ref "C35") (pin "2") (pinfunction "2_2") (pintype "passive"))
      (node (ref "C36") (pin "1") (pinfunction "1_1") (pintype "passive"))
      (node (ref "C37") (pin "2") (pinfunction "2_2") (pintype "passive"))
      (node (ref "C38") (pin "1") (pinfunction "1_1") (pintype "passive"))
      (node (ref "C39") (pin "1") (pinfunction "1_1") (pintype "passive"))
      (node (ref "C41") (pin "2") (pinfunction "2_2") (pintype "passive"))
      (node (ref "C42") (pin "1") (pinfunction "1_1") (pintype "passive"))
      (node (ref "C43") (pin "C") (pinfunction "C_C") (pintype "bidirectional"))
      (node (ref "C5") (pin "2") (pinfunction "2_2") (pintype "passive"))
      (node (ref "C6") (pin "2") (pinfunction "2_2") (pintype "passive"))
      (node (ref "C9") (pin "1") (pinfunction "1_1") (pintype "passive"))
      (node (ref "D1") (pin "A") (pinfunction "A_A") (pintype "passive"))
      (node (ref "D13") (pin "A") (pinfunction "A_A") (pintype "passive"))
      (node (ref "D14") (pin "A") (pinfunction "A_A") (pintype "passive"))
      (node (ref "JP1") (pin "2") (pinfunction "2_2") (pintype "passive"))
      (node (ref "R3") (pin "1") (pinfunction "1_1") (pintype "passive"))
      (node (ref "R38") (pin "1") (pinfunction "1_1") (pintype "passive"))
      (node (ref "R4") (pin "1") (pinfunction "1_1") (pintype "passive"))
      (node (ref "R49") (pin "1") (pinfunction "1_1") (pintype "passive"))
      (node (ref "R5") (pin "1") (pinfunction "1_1") (pintype "passive"))
      (node (ref "R50") (pin "1") (pinfunction "1_1") (pintype "passive"))
      (node (ref "R51") (pin "1") (pinfunction "1_1") (pintype "passive"))
      (node (ref "R52") (pin "1") (pinfunction "1_1") (pintype "passive"))
      (node (ref "R57") (pin "1") (pinfunction "1_1") (pintype "passive"))
      (node (ref "R58") (pin "1") (pinfunction "1_1") (pintype "passive"))
      (node (ref "R59") (pin "1") (pinfunction "1_1") (pintype "passive"))
      (node (ref "R60") (pin "1") (pinfunction "1_1") (pintype "passive"))
      (node (ref "R7") (pin "1") (pinfunction "1_1") (pintype "passive"))
      (node (ref "U1") (pin "11") (pinfunction "EP_11") (pintype "passive"))
      (node (ref "U1") (pin "9") (pinfunction "GND_9") (pintype "passive"))
      (node (ref "U11") (pin "2") (pinfunction "2_2") (pintype "bidirectional"))
      (node (ref "U11") (pin "5") (pinfunction "5_5") (pintype "bidirectional"))
      (node (ref "U3") (pin "A0") (pinfunction "A0_A0") (pintype "bidirectional"))
      (node (ref "U3") (pin "A1") (pinfunction "A1_A1") (pintype "bidirectional"))
      (node (ref "U3") (pin "A2") (pinfunction "A2_A2") (pintype "bidirectional"))
      (node (ref "U3") (pin "A3") (pinfunction "A3_A3") (pintype "bidirectional"))
      (node (ref "U3") (pin "C0") (pinfunction "C0_C0") (pintype "bidirectional"))
      (node (ref "U3") (pin "NC") (pinfunction "NC_NC") (pintype "bidirectional"))
      (node (ref "U3") (pin "TOS") (pinfunction "TOS_TOS") (pintype "bidirectional"))
      (node (ref "U3") (pin "V-") (pinfunction "V-_V-") (pintype "bidirectional"))
      (node (ref "U4") (pin "4") (pinfunction "GND_4") (pintype "passive"))
      (node (ref "U5") (pin "4") (pinfunction "GND1_4") (pintype "input"))
      (node (ref "U6") (pin "109") (pinfunction "VRL_109") (pintype "power_in"))
      (node (ref "U6") (pin "110") (pinfunction "VSSA*_110") (pintype "power_in"))
      (node (ref "U6") (pin "138") (pinfunction "VSSX1_138") (pintype "bidirectional"))
      (node (ref "U6") (pin "16") (pinfunction "VSS1_16") (pintype "power_in"))
      (node (ref "U6") (pin "27") (pinfunction "VSSX2*_27") (pintype "power_in"))
      (node (ref "U6") (pin "52") (pinfunction "VSSR1*_52") (pintype "power_in"))
      (node (ref "U6") (pin "57") (pinfunction "VSSPLL_57") (pintype "power_in"))
      (node (ref "U6") (pin "60") (pinfunction "TEST*_60") (pintype "power_in"))
      (node (ref "U6") (pin "81") (pinfunction "VSSR2*_81") (pintype "power_in"))
      (node (ref "U6") (pin "88") (pinfunction "VSS2_88") (pintype "power_in"))
      (node (ref "U7") (pin "11") (pinfunction "V-_11") (pintype "power_in"))
      (node (ref "U8") (pin "11") (pinfunction "V-_11") (pintype "power_in"))
      (node (ref "U9") (pin "11") (pinfunction "V-_11") (pintype "power_in"))
      (node (ref "X1") (pin "1") (pinfunction "1_1") (pintype "bidirectional"))
      (node (ref "X1") (pin "20") (pinfunction "20_20") (pintype "bidirectional"))
      (node (ref "X1") (pin "4") (pinfunction "4_4") (pintype "bidirectional"))
      (node (ref "X2") (pin "18") (pinfunction "18_18") (pintype "bidirectional"))
      (node (ref "X5") (pin "2") (pinfunction "GND_2") (pintype "bidirectional"))
    )
    (net (code "60") (name "GND_BUS") (class "Default")
      (node (ref "C40") (pin "2") (pinfunction "2_2") (pintype "passive"))
      (node (ref "C7") (pin "2") (pinfunction "2_2") (pintype "passive"))
      (node (ref "C8") (pin "2") (pinfunction "2_2") (pintype "passive"))
      (node (ref "U10") (pin "3") (pinfunction "3_3") (pintype "bidirectional"))
      (node (ref "U2") (pin "3") (pinfunction "3_3") (pintype "bidirectional"))
      (node (ref "U5") (pin "5") (pinfunction "GND2_5") (pintype "input"))
      (node (ref "X3") (pin "2") (pinfunction "2_2") (pintype "bidirectional"))
      (node (ref "X4") (pin "2") (pinfunction "2_2") (pintype "bidirectional"))
    )
    (net (code "61") (name "Net-(C1-Pad1)") (class "Default")
      (node (ref "C1") (pin "1") (pinfunction "1_1") (pintype "passive"))
      (node (ref "R1") (pin "1") (pinfunction "1_1") (pintype "passive"))
    )
    (net (code "62") (name "Net-(C8-Pad1)") (class "Default")
      (node (ref "C8") (pin "1") (pinfunction "1_1") (pintype "passive"))
      (node (ref "R40") (pin "2") (pinfunction "2_2") (pintype "passive"))
      (node (ref "R41") (pin "2") (pinfunction "2_2") (pintype "passive"))
    )
    (net (code "63") (name "Net-(C29-Pad1)") (class "Default")
      (node (ref "C29") (pin "1") (pinfunction "1_1") (pintype "passive"))
      (node (ref "R34") (pin "1") (pinfunction "1_1") (pintype "passive"))
      (node (ref "U3") (pin "V+") (pinfunction "V+_V+") (pintype "bidirectional"))
    )
    (net (code "64") (name "Net-(C31-Pad1)") (class "Default")
      (node (ref "C31") (pin "1") (pinfunction "1_1") (pintype "passive"))
      (node (ref "U3") (pin "VREF") (pinfunction "VREF_VREF") (pintype "bidirectional"))
    )
    (net (code "65") (name "Net-(C32-Pad1)") (class "Default")
      (node (ref "C32") (pin "1") (pinfunction "1_1") (pintype "passive"))
      (node (ref "R66") (pin "2") (pinfunction "2_2") (pintype "passive"))
      (node (ref "R67") (pin "2") (pinfunction "2_2") (pintype "passive"))
      (node (ref "R68") (pin "2") (pinfunction "2_2") (pintype "passive"))
      (node (ref "U3") (pin "VREG") (pinfunction "VREG_VREG") (pintype "bidirectional"))
    )
    (net (code "66") (name "Net-(LED1-PadC)") (class "Default")
      (node (ref "LED1") (pin "C") (pinfunction "C_C") (pintype "passive"))
      (node (ref "R38") (pin "2") (pinfunction "2_2") (pintype "passive"))
    )
    (net (code "67") (name "Net-(LED2-PadC)") (class "Default")
      (node (ref "LED2") (pin "C") (pinfunction "C_C") (pintype "passive"))
      (node (ref "R42") (pin "2") (pinfunction "2_2") (pintype "passive"))
    )
    (net (code "68") (name "Net-(LED3-PadC)") (class "Default")
      (node (ref "LED3") (pin "C") (pinfunction "C_C") (pintype "passive"))
      (node (ref "R43") (pin "2") (pinfunction "2_2") (pintype "passive"))
    )
    (net (code "69") (name "Net-(LED4-PadC)") (class "Default")
      (node (ref "LED4") (pin "C") (pinfunction "C_C") (pintype "passive"))
      (node (ref "R44") (pin "2") (pinfunction "2_2") (pintype "passive"))
    )
    (net (code "70") (name "Net-(R6-Pad1)") (class "Default")
      (node (ref "R6") (pin "1") (pinfunction "1_1") (pintype "passive"))
      (node (ref "R7") (pin "2") (pinfunction "2_2") (pintype "passive"))
      (node (ref "R8") (pin "2") (pinfunction "2_2") (pintype "passive"))
      (node (ref "U2") (pin "6") (pinfunction "6_6") (pintype "bidirectional"))
    )
    (net (code "71") (name "Net-(R39-Pad2)") (class "Default")
      (node (ref "R39") (pin "2") (pinfunction "2_2") (pintype "passive"))
      (node (ref "U2") (pin "1") (pinfunction "1_1") (pintype "bidirectional"))
    )
    (net (code "72") (name "Net-(R45-Pad2)") (class "Default")
      (node (ref "R45") (pin "2") (pinfunction "2_2") (pintype "passive"))
      (node (ref "R57") (pin "2") (pinfunction "2_2") (pintype "passive"))
      (node (ref "R61") (pin "1") (pinfunction "1_1") (pintype "passive"))
      (node (ref "U11") (pin "4") (pinfunction "4_4") (pintype "bidirectional"))
      (node (ref "X6") (pin "1") (pinfunction "1_1") (pintype "passive"))
    )
    (net (code "73") (name "Net-(R46-Pad2)") (class "Default")
      (node (ref "R46") (pin "2") (pinfunction "2_2") (pintype "passive"))
      (node (ref "R58") (pin "2") (pinfunction "2_2") (pintype "passive"))
      (node (ref "R62") (pin "1") (pinfunction "1_1") (pintype "passive"))
      (node (ref "U11") (pin "6") (pinfunction "6_6") (pintype "bidirectional"))
      (node (ref "X6") (pin "2") (pinfunction "2_2") (pintype "passive"))
    )
    (net (code "74") (name "Net-(R47-Pad2)") (class "Default")
      (node (ref "R47") (pin "2") (pinfunction "2_2") (pintype "passive"))
      (node (ref "R59") (pin "2") (pinfunction "2_2") (pintype "passive"))
      (node (ref "R63") (pin "1") (pinfunction "1_1") (pintype "passive"))
      (node (ref "U11") (pin "1") (pinfunction "1_1") (pintype "bidirectional"))
      (node (ref "X6") (pin "3") (pinfunction "3_3") (pintype "passive"))
    )
    (net (code "75") (name "Net-(R48-Pad2)") (class "Default")
      (node (ref "R48") (pin "2") (pinfunction "2_2") (pintype "passive"))
      (node (ref "R60") (pin "2") (pinfunction "2_2") (pintype "passive"))
      (node (ref "R64") (pin "1") (pinfunction "1_1") (pintype "passive"))
      (node (ref "U11") (pin "3") (pinfunction "3_3") (pintype "bidirectional"))
      (node (ref "X6") (pin "4") (pinfunction "4_4") (pintype "passive"))
    )
    (net (code "76") (name "Net-(U1-BOOT)") (class "Default")
      (node (ref "C4") (pin "1") (pinfunction "1_1") (pintype "passive"))
      (node (ref "U1") (pin "1") (pinfunction "BOOT_1") (pintype "output"))
    )
    (net (code "77") (name "Net-(U1-COMP)") (class "Default")
      (node (ref "C2") (pin "1") (pinfunction "1_1") (pintype "passive"))
      (node (ref "R1") (pin "2") (pinfunction "2_2") (pintype "passive"))
      (node (ref "U1") (pin "8") (pinfunction "COMP_8") (pintype "output"))
    )
    (net (code "78") (name "Net-(U1-EN)") (class "Default")
      (node (ref "R5") (pin "2") (pinfunction "2_2") (pintype "passive"))
      (node (ref "R8") (pin "1") (pinfunction "1_1") (pintype "passive"))
      (node (ref "U1") (pin "3") (pinfunction "EN_3") (pintype "input"))
      (node (ref "U2") (pin "4") (pinfunction "4_4") (pintype "bidirectional"))
    )
    (net (code "79") (name "Net-(U1-PH)") (class "Default")
      (node (ref "C4") (pin "2") (pinfunction "2_2") (pintype "passive"))
      (node (ref "D1") (pin "C") (pinfunction "C_C") (pintype "passive"))
      (node (ref "L1") (pin "P$2") (pinfunction "P$2_P$2") (pintype "bidirectional"))
      (node (ref "U1") (pin "10") (pinfunction "PH_10") (pintype "input"))
    )
    (net (code "80") (name "Net-(U1-RT{slash}CLK)") (class "Default")
      (node (ref "R4") (pin "2") (pinfunction "2_2") (pintype "passive"))
      (node (ref "U1") (pin "5") (pinfunction "RT/CLK_5") (pintype "input"))
    )
    (net (code "81") (name "Net-(U1-SS{slash}TR)") (class "Default")
      (node (ref "C3") (pin "1") (pinfunction "1_1") (pintype "passive"))
      (node (ref "U1") (pin "4") (pinfunction "SS/TR_4") (pintype "input"))
    )
    (net (code "82") (name "Net-(U1-VSENSE)") (class "Default")
      (node (ref "R2") (pin "1") (pinfunction "1_1") (pintype "passive"))
      (node (ref "R3") (pin "2") (pinfunction "2_2") (pintype "passive"))
      (node (ref "U1") (pin "7") (pinfunction "VSENSE_7") (pintype "input"))
    )
    (net (code "83") (name "Net-(U4-1A)") (class "Default")
      (node (ref "R53") (pin "2") (pinfunction "2_2") (pintype "passive"))
      (node (ref "U4") (pin "1") (pinfunction "1A_1") (pintype "input"))
      (node (ref "U6") (pin "10") (pinfunction "PK0_10") (pintype "bidirectional"))
    )
    (net (code "84") (name "Net-(U4-1Y)") (class "Default")
      (node (ref "R44") (pin "1") (pinfunction "1_1") (pintype "passive"))
      (node (ref "U4") (pin "7") (pinfunction "1Y_7") (pintype "output"))
    )
    (net (code "85") (name "Net-(U4-2A)") (class "Default")
      (node (ref "R55") (pin "2") (pinfunction "2_2") (pintype "passive"))
      (node (ref "U4") (pin "3") (pinfunction "2A_3") (pintype "input"))
      (node (ref "U6") (pin "9") (pinfunction "PK1_9") (pintype "bidirectional"))
    )
    (net (code "86") (name "Net-(U4-2Y)") (class "Default")
      (node (ref "R43") (pin "1") (pinfunction "1_1") (pintype "passive"))
      (node (ref "U4") (pin "5") (pinfunction "2Y_5") (pintype "output"))
    )
    (net (code "87") (name "Net-(U4-3A)") (class "Default")
      (node (ref "R54") (pin "2") (pinfunction "2_2") (pintype "passive"))
      (node (ref "U4") (pin "6") (pinfunction "3A_6") (pintype "input"))
      (node (ref "U6") (pin "8") (pinfunction "PK2_8") (pintype "bidirectional"))
    )
    (net (code "88") (name "Net-(U4-3Y)") (class "Default")
      (node (ref "R42") (pin "1") (pinfunction "1_1") (pintype "passive"))
      (node (ref "U4") (pin "2") (pinfunction "3Y_2") (pintype "output"))
    )
    (net (code "89") (name "Net-(U6-EXTAL)") (class "Default")
      (node (ref "C27") (pin "1") (pinfunction "1_1") (pintype "passive"))
      (node (ref "U6") (pin "58") (pinfunction "EXTAL_58") (pintype "passive"))
      (node (ref "Y1") (pin "P$2") (pinfunction "2_P$2") (pintype "passive"))
    )
    (net (code "90") (name "Net-(U6-PD1)") (class "Default")
      (node (ref "R65") (pin "1") (pinfunction "1_1") (pintype "passive"))
      (node (ref "U6") (pin "66") (pinfunction "PD1_66") (pintype "bidirectional"))
      (node (ref "X1") (pin "17") (pinfunction "17_17") (pintype "bidirectional"))
    )
    (net (code "91") (name "Net-(U6-PJ4)") (class "Default")
      (node (ref "R45") (pin "1") (pinfunction "1_1") (pintype "passive"))
      (node (ref "U6") (pin "131") (pinfunction "PJ4_131") (pintype "bidirectional"))
    )
    (net (code "92") (name "Net-(U6-PJ5)") (class "Default")
      (node (ref "R46") (pin "1") (pinfunction "1_1") (pintype "passive"))
      (node (ref "U6") (pin "130") (pinfunction "PJ5_130") (pintype "bidirectional"))
    )
    (net (code "93") (name "Net-(U6-PJ6)") (class "Default")
      (node (ref "R47") (pin "1") (pinfunction "1_1") (pintype "passive"))
      (node (ref "U6") (pin "129") (pinfunction "PJ6_129") (pintype "bidirectional"))
    )
    (net (code "94") (name "Net-(U6-PJ7)") (class "Default")
      (node (ref "R48") (pin "1") (pinfunction "1_1") (pintype "passive"))
      (node (ref "U6") (pin "128") (pinfunction "PJ7_128") (pintype "bidirectional"))
    )
    (net (code "95") (name "Net-(U6-PS0)") (class "Default")
      (node (ref "R49") (pin "2") (pinfunction "2_2") (pintype "passive"))
      (node (ref "U6") (pin "119") (pinfunction "PS0_119") (pintype "bidirectional"))
    )
    (net (code "96") (name "Net-(U6-PS1)") (class "Default")
      (node (ref "R50") (pin "2") (pinfunction "2_2") (pintype "passive"))
      (node (ref "U6") (pin "120") (pinfunction "PS1_120") (pintype "bidirectional"))
    )
    (net (code "97") (name "Net-(U6-PS2)") (class "Default")
      (node (ref "R51") (pin "2") (pinfunction "2_2") (pintype "passive"))
      (node (ref "U6") (pin "121") (pinfunction "PS2_121") (pintype "bidirectional"))
    )
    (net (code "98") (name "Net-(U6-PS3)") (class "Default")
      (node (ref "R52") (pin "2") (pinfunction "2_2") (pintype "passive"))
      (node (ref "U6") (pin "122") (pinfunction "PS3_122") (pintype "bidirectional"))
    )
    (net (code "99") (name "Net-(U6-RESET)") (class "Default")
      (node (ref "C35") (pin "1") (pinfunction "1_1") (pintype "passive"))
      (node (ref "R37") (pin "1") (pinfunction "1_1") (pintype "passive"))
      (node (ref "U6") (pin "54") (pinfunction "RESET_54") (pintype "bidirectional"))
      (node (ref "X5") (pin "4") (pinfunction "~{RESET}_4") (pintype "bidirectional"))
    )
    (net (code "100") (name "Net-(U6-VDD1*)") (class "Default")
      (node (ref "C39") (pin "2") (pinfunction "2_2") (pintype "passive"))
      (node (ref "U6") (pin "15") (pinfunction "VDD1*_15") (pintype "power_in"))
    )
    (net (code "101") (name "Net-(U6-VDD2*)") (class "Default")
      (node (ref "C37") (pin "1") (pinfunction "1_1") (pintype "passive"))
      (node (ref "U6") (pin "87") (pinfunction "VDD2*_87") (pintype "power_in"))
    )
    (net (code "102") (name "Net-(U6-VDDPLL*)") (class "Default")
      (node (ref "C36") (pin "2") (pinfunction "2_2") (pintype "passive"))
      (node (ref "U6") (pin "55") (pinfunction "VDDPLL*_55") (pintype "power_in"))
      (node (ref "U6") (pin "56") (pinfunction "XFC*_56") (pintype "power_in"))
    )
    (net (code "103") (name "Net-(U6-XTAL)") (class "Default")
      (node (ref "C28") (pin "1") (pinfunction "1_1") (pintype "passive"))
      (node (ref "U6") (pin "59") (pinfunction "XTAL_59") (pintype "passive"))
      (node (ref "Y1") (pin "P$1") (pinfunction "1_P$1") (pintype "passive"))
    )
    (net (code "104") (name "V1") (class "Default")
      (node (ref "R20") (pin "1") (pinfunction "1_1") (pintype "passive"))
      (node (ref "X1") (pin "5") (pinfunction "5_5") (pintype "bidirectional"))
      (node (ref "X2") (pin "19") (pinfunction "19_19") (pintype "bidirectional"))
    )
    (net (code "105") (name "V2") (class "Default")
      (node (ref "R19") (pin "1") (pinfunction "1_1") (pintype "passive"))
      (node (ref "X1") (pin "6") (pinfunction "6_6") (pintype "bidirectional"))
      (node (ref "X2") (pin "20") (pinfunction "20_20") (pintype "bidirectional"))
    )
    (net (code "106") (name "V3") (class "Default")
      (node (ref "R18") (pin "1") (pinfunction "1_1") (pintype "passive"))
      (node (ref "X1") (pin "7") (pinfunction "7_7") (pintype "bidirectional"))
      (node (ref "X2") (pin "21") (pinfunction "21_21") (pintype "bidirectional"))
    )
    (net (code "107") (name "V4") (class "Default")
      (node (ref "R17") (pin "1") (pinfunction "1_1") (pintype "passive"))
      (node (ref "X1") (pin "8") (pinfunction "8_8") (pintype "bidirectional"))
      (node (ref "X2") (pin "22") (pinfunction "22_22") (pintype "bidirectional"))
    )
    (net (code "108") (name "V5") (class "Default")
      (node (ref "R16") (pin "1") (pinfunction "1_1") (pintype "passive"))
      (node (ref "X1") (pin "9") (pinfunction "9_9") (pintype "bidirectional"))
      (node (ref "X2") (pin "23") (pinfunction "23_23") (pintype "bidirectional"))
    )
    (net (code "109") (name "V6") (class "Default")
      (node (ref "R15") (pin "1") (pinfunction "1_1") (pintype "passive"))
      (node (ref "X1") (pin "10") (pinfunction "10_10") (pintype "bidirectional"))
      (node (ref "X2") (pin "24") (pinfunction "24_24") (pintype "bidirectional"))
    )
    (net (code "110") (name "V7") (class "Default")
      (node (ref "R14") (pin "1") (pinfunction "1_1") (pintype "passive"))
      (node (ref "X1") (pin "11") (pinfunction "11_11") (pintype "bidirectional"))
      (node (ref "X2") (pin "25") (pinfunction "25_25") (pintype "bidirectional"))
    )
    (net (code "111") (name "V8") (class "Default")
      (node (ref "R13") (pin "1") (pinfunction "1_1") (pintype "passive"))
      (node (ref "X1") (pin "12") (pinfunction "12_12") (pintype "bidirectional"))
      (node (ref "X2") (pin "26") (pinfunction "26_26") (pintype "bidirectional"))
    )
    (net (code "112") (name "V9") (class "Default")
      (node (ref "R12") (pin "1") (pinfunction "1_1") (pintype "passive"))
      (node (ref "X1") (pin "13") (pinfunction "13_13") (pintype "bidirectional"))
      (node (ref "X2") (pin "27") (pinfunction "27_27") (pintype "bidirectional"))
    )
    (net (code "113") (name "V10") (class "Default")
      (node (ref "R11") (pin "1") (pinfunction "1_1") (pintype "passive"))
      (node (ref "X1") (pin "14") (pinfunction "14_14") (pintype "bidirectional"))
      (node (ref "X2") (pin "28") (pinfunction "28_28") (pintype "bidirectional"))
    )
    (net (code "114") (name "V11") (class "Default")
      (node (ref "R10") (pin "1") (pinfunction "1_1") (pintype "passive"))
      (node (ref "X1") (pin "15") (pinfunction "15_15") (pintype "bidirectional"))
      (node (ref "X2") (pin "29") (pinfunction "29_29") (pintype "bidirectional"))
    )
    (net (code "115") (name "V12") (class "Default")
      (node (ref "FB") (pin "1") (pinfunction "1_1") (pintype "passive"))
      (node (ref "X1") (pin "16") (pinfunction "16_16") (pintype "bidirectional"))
      (node (ref "X2") (pin "30") (pinfunction "30_30") (pintype "bidirectional"))
    )
    (net (code "116") (name "V12_FERRITE") (class "Default")
      (node (ref "C5") (pin "1") (pinfunction "1_1") (pintype "passive"))
      (node (ref "C6") (pin "1") (pinfunction "1_1") (pintype "passive"))
      (node (ref "D14") (pin "C") (pinfunction "C_C") (pintype "passive"))
      (node (ref "FB") (pin "2") (pinfunction "2_2") (pintype "passive"))
      (node (ref "R34") (pin "2") (pinfunction "2_2") (pintype "passive"))
      (node (ref "R6") (pin "2") (pinfunction "2_2") (pintype "passive"))
      (node (ref "R9") (pin "1") (pinfunction "1_1") (pintype "passive"))
      (node (ref "U1") (pin "2") (pinfunction "VIN_2") (pintype "power_in"))
    )
    (net (code "117") (name "VCC") (class "Default")
      (node (ref "C10") (pin "1") (pinfunction "1_1") (pintype "passive"))
      (node (ref "C11") (pin "2") (pinfunction "2_2") (pintype "passive"))
      (node (ref "C12") (pin "1") (pinfunction "1_1") (pintype "passive"))
      (node (ref "C13") (pin "1") (pinfunction "1_1") (pintype "passive"))
      (node (ref "C14") (pin "1") (pinfunction "1_1") (pintype "passive"))
      (node (ref "C34") (pin "2") (pinfunction "2_2") (pintype "passive"))
      (node (ref "C38") (pin "2") (pinfunction "2_2") (pintype "passive"))
      (node (ref "C41") (pin "1") (pinfunction "1_1") (pintype "passive"))
      (node (ref "C42") (pin "2") (pinfunction "2_2") (pintype "passive"))
      (node (ref "C43") (pin "A") (pinfunction "A_A") (pintype "bidirectional"))
      (node (ref "C9") (pin "2") (pinfunction "2_2") (pintype "passive"))
      (node (ref "JP1") (pin "1") (pinfunction "1_1") (pintype "passive"))
      (node (ref "L1") (pin "P$1") (pinfunction "P$1_P$1") (pintype "bidirectional"))
      (node (ref "LED1") (pin "A") (pinfunction "A_A") (pintype "passive"))
      (node (ref "LED2") (pin "A") (pinfunction "A_A") (pintype "passive"))
      (node (ref "LED3") (pin "A") (pinfunction "A_A") (pintype "passive"))
      (node (ref "LED4") (pin "A") (pinfunction "A_A") (pintype "passive"))
      (node (ref "R2") (pin "2") (pinfunction "2_2") (pintype "passive"))
      (node (ref "R22") (pin "2") (pinfunction "2_2") (pintype "passive"))
      (node (ref "R23") (pin "2") (pinfunction "2_2") (pintype "passive"))
      (node (ref "R24") (pin "2") (pinfunction "2_2") (pintype "passive"))
      (node (ref "R25") (pin "2") (pinfunction "2_2") (pintype "passive"))
      (node (ref "R26") (pin "2") (pinfunction "2_2") (pintype "passive"))
      (node (ref "R27") (pin "2") (pinfunction "2_2") (pintype "passive"))
      (node (ref "R28") (pin "2") (pinfunction "2_2") (pintype "passive"))
      (node (ref "R29") (pin "2") (pinfunction "2_2") (pintype "passive"))
      (node (ref "R30") (pin "2") (pinfunction "2_2") (pintype "passive"))
      (node (ref "R31") (pin "2") (pinfunction "2_2") (pintype "passive"))
      (node (ref "R32") (pin "2") (pinfunction "2_2") (pintype "passive"))
      (node (ref "R33") (pin "2") (pinfunction "2_2") (pintype "passive"))
      (node (ref "R35") (pin "1") (pinfunction "1_1") (pintype "passive"))
      (node (ref "R37") (pin "2") (pinfunction "2_2") (pintype "passive"))
      (node (ref "R53") (pin "1") (pinfunction "1_1") (pintype "passive"))
      (node (ref "R54") (pin "1") (pinfunction "1_1") (pintype "passive"))
      (node (ref "R55") (pin "1") (pinfunction "1_1") (pintype "passive"))
      (node (ref "R56") (pin "2") (pinfunction "2_2") (pintype "passive"))
      (node (ref "R61") (pin "2") (pinfunction "2_2") (pintype "passive"))
      (node (ref "R62") (pin "2") (pinfunction "2_2") (pintype "passive"))
      (node (ref "R63") (pin "2") (pinfunction "2_2") (pintype "passive"))
      (node (ref "R64") (pin "2") (pinfunction "2_2") (pintype "passive"))
      (node (ref "R65") (pin "2") (pinfunction "2_2") (pintype "passive"))
      (node (ref "U4") (pin "8") (pinfunction "VCC_8") (pintype "power_in"))
      (node (ref "U5") (pin "1") (pinfunction "VCC1_1") (pintype "input"))
      (node (ref "U6") (pin "107") (pinfunction "VDDA*_107") (pintype "power_in"))
      (node (ref "U6") (pin "108") (pinfunction "VRH_108") (pintype "power_in"))
      (node (ref "U6") (pin "127") (pinfunction "VREGEN_127") (pintype "bidirectional"))
      (node (ref "U6") (pin "139") (pinfunction "VDDX1_139") (pintype "power_in"))
      (node (ref "U6") (pin "26") (pinfunction "VDDX2*_26") (pintype "power_in"))
      (node (ref "U6") (pin "53") (pinfunction "VDDR1*_53") (pintype "power_in"))
      (node (ref "U6") (pin "82") (pinfunction "VDDR2*_82") (pintype "power_in"))
      (node (ref "U7") (pin "4") (pinfunction "V+_4") (pintype "power_in"))
      (node (ref "U8") (pin "4") (pinfunction "V+_4") (pintype "power_in"))
      (node (ref "U9") (pin "4") (pinfunction "V+_4") (pintype "power_in"))
      (node (ref "X5") (pin "6") (pinfunction "VDD_6") (pintype "bidirectional"))
    )
    (net (code "118") (name "unconnected-(U1-PWRGD-Pad6)") (class "Default")
      (node (ref "U1") (pin "6") (pinfunction "PWRGD_6") (pintype "output"))
    )
    (net (code "119") (name "unconnected-(U3-PadGPIO1)") (class "Default")
      (node (ref "U3") (pin "GPIO1") (pinfunction "GPIO1_GPIO1") (pintype "bidirectional"))
    )
    (net (code "120") (name "unconnected-(U3-PadGPIO2)") (class "Default")
      (node (ref "U3") (pin "GPIO2") (pinfunction "GPIO2_GPIO2") (pintype "bidirectional"))
    )
    (net (code "121") (name "unconnected-(U3-PadVTEMP1)") (class "Default")
      (node (ref "U3") (pin "VTEMP1") (pinfunction "VTEMP1_VTEMP1") (pintype "bidirectional"))
    )
    (net (code "122") (name "unconnected-(U3-PadVTEMP2)") (class "Default")
      (node (ref "U3") (pin "VTEMP2") (pinfunction "VTEMP2_VTEMP2") (pintype "bidirectional"))
    )
    (net (code "123") (name "unconnected-(U3-PadWDTB)") (class "Default")
      (node (ref "U3") (pin "WDTB") (pinfunction "WDTB_WDTB") (pintype "bidirectional"))
    )
    (net (code "124") (name "unconnected-(U6-PA0-Pad73)") (class "Default")
      (node (ref "U6") (pin "73") (pinfunction "PA0_73") (pintype "bidirectional"))
    )
    (net (code "125") (name "unconnected-(U6-PA1-Pad74)") (class "Default")
      (node (ref "U6") (pin "74") (pinfunction "PA1_74") (pintype "bidirectional"))
    )
    (net (code "126") (name "unconnected-(U6-PA2-Pad75)") (class "Default")
      (node (ref "U6") (pin "75") (pinfunction "PA2_75") (pintype "bidirectional"))
    )
    (net (code "127") (name "unconnected-(U6-PA3-Pad76)") (class "Default")
      (node (ref "U6") (pin "76") (pinfunction "PA3_76") (pintype "bidirectional"))
    )
    (net (code "128") (name "unconnected-(U6-PA4-Pad77)") (class "Default")
      (node (ref "U6") (pin "77") (pinfunction "PA4_77") (pintype "bidirectional"))
    )
    (net (code "129") (name "unconnected-(U6-PA5-Pad78)") (class "Default")
      (node (ref "U6") (pin "78") (pinfunction "PA5_78") (pintype "bidirectional"))
    )
    (net (code "130") (name "unconnected-(U6-PA6-Pad79)") (class "Default")
      (node (ref "U6") (pin "79") (pinfunction "PA6_79") (pintype "bidirectional"))
    )
    (net (code "131") (name "unconnected-(U6-PA7-Pad80)") (class "Default")
      (node (ref "U6") (pin "80") (pinfunction "PA7_80") (pintype "bidirectional"))
    )
    (net (code "132") (name "unconnected-(U6-PAD12-AN12-Pad98)") (class "Default")
      (node (ref "U6") (pin "98") (pinfunction "PAD12-AN12_98") (pintype "bidirectional"))
    )
    (net (code "133") (name "unconnected-(U6-PAD13-AN13-Pad100)") (class "Default")
      (node (ref "U6") (pin "100") (pinfunction "PAD13-AN13_100") (pintype "bidirectional"))
    )
    (net (code "134") (name "unconnected-(U6-PAD14-AN14-Pad102)") (class "Default")
      (node (ref "U6") (pin "102") (pinfunction "PAD14-AN14_102") (pintype "bidirectional"))
    )
    (net (code "135") (name "unconnected-(U6-PAD15-AN15-Pad104)") (class "Default")
      (node (ref "U6") (pin "104") (pinfunction "PAD15-AN15_104") (pintype "bidirectional"))
    )
    (net (code "136") (name "unconnected-(U6-PAD16-AN16-Pad105)") (class "Default")
      (node (ref "U6") (pin "105") (pinfunction "PAD16-AN16_105") (pintype "bidirectional"))
    )
    (net (code "137") (name "unconnected-(U6-PAD17-AN17-Pad106)") (class "Default")
      (node (ref "U6") (pin "106") (pinfunction "PAD17-AN17_106") (pintype "bidirectional"))
    )
    (net (code "138") (name "unconnected-(U6-PAD18-Pad111)") (class "Default")
      (node (ref "U6") (pin "111") (pinfunction "PAD18_111") (pintype "bidirectional"))
    )
    (net (code "139") (name "unconnected-(U6-PAD19-Pad112)") (class "Default")
      (node (ref "U6") (pin "112") (pinfunction "PAD19_112") (pintype "bidirectional"))
    )
    (net (code "140") (name "unconnected-(U6-PAD20-Pad113)") (class "Default")
      (node (ref "U6") (pin "113") (pinfunction "PAD20_113") (pintype "bidirectional"))
    )
    (net (code "141") (name "unconnected-(U6-PAD21-Pad114)") (class "Default")
      (node (ref "U6") (pin "114") (pinfunction "PAD21_114") (pintype "bidirectional"))
    )
    (net (code "142") (name "unconnected-(U6-PAD22-Pad115)") (class "Default")
      (node (ref "U6") (pin "115") (pinfunction "PAD22_115") (pintype "bidirectional"))
    )
    (net (code "143") (name "unconnected-(U6-PAD23-Pad116)") (class "Default")
      (node (ref "U6") (pin "116") (pinfunction "PAD23_116") (pintype "bidirectional"))
    )
    (net (code "144") (name "unconnected-(U6-PB0-Pad32)") (class "Default")
      (node (ref "U6") (pin "32") (pinfunction "PB0_32") (pintype "bidirectional"))
    )
    (net (code "145") (name "unconnected-(U6-PB1-Pad33)") (class "Default")
      (node (ref "U6") (pin "33") (pinfunction "PB1_33") (pintype "bidirectional"))
    )
    (net (code "146") (name "unconnected-(U6-PB2-Pad34)") (class "Default")
      (node (ref "U6") (pin "34") (pinfunction "PB2_34") (pintype "bidirectional"))
    )
    (net (code "147") (name "unconnected-(U6-PB3-Pad35)") (class "Default")
      (node (ref "U6") (pin "35") (pinfunction "PB3_35") (pintype "bidirectional"))
    )
    (net (code "148") (name "unconnected-(U6-PB4-Pad36)") (class "Default")
      (node (ref "U6") (pin "36") (pinfunction "PB4_36") (pintype "bidirectional"))
    )
    (net (code "149") (name "unconnected-(U6-PB5-Pad37)") (class "Default")
      (node (ref "U6") (pin "37") (pinfunction "PB5_37") (pintype "bidirectional"))
    )
    (net (code "150") (name "unconnected-(U6-PB6-Pad38)") (class "Default")
      (node (ref "U6") (pin "38") (pinfunction "PB6_38") (pintype "bidirectional"))
    )
    (net (code "151") (name "unconnected-(U6-PB7-Pad39)") (class "Default")
      (node (ref "U6") (pin "39") (pinfunction "PB7_39") (pintype "bidirectional"))
    )
    (net (code "152") (name "unconnected-(U6-PC0-Pad28)") (class "Default")
      (node (ref "U6") (pin "28") (pinfunction "PC0_28") (pintype "bidirectional"))
    )
    (net (code "153") (name "unconnected-(U6-PC1-Pad29)") (class "Default")
      (node (ref "U6") (pin "29") (pinfunction "PC1_29") (pintype "bidirectional"))
    )
    (net (code "154") (name "unconnected-(U6-PC2-Pad30)") (class "Default")
      (node (ref "U6") (pin "30") (pinfunction "PC2_30") (pintype "bidirectional"))
    )
    (net (code "155") (name "unconnected-(U6-PC3-Pad31)") (class "Default")
      (node (ref "U6") (pin "31") (pinfunction "PC3_31") (pintype "bidirectional"))
    )
    (net (code "156") (name "unconnected-(U6-PC4-Pad40)") (class "Default")
      (node (ref "U6") (pin "40") (pinfunction "PC4_40") (pintype "bidirectional"))
    )
    (net (code "157") (name "unconnected-(U6-PC5-Pad41)") (class "Default")
      (node (ref "U6") (pin "41") (pinfunction "PC5_41") (pintype "bidirectional"))
    )
    (net (code "158") (name "unconnected-(U6-PC6-Pad42)") (class "Default")
      (node (ref "U6") (pin "42") (pinfunction "PC6_42") (pintype "bidirectional"))
    )
    (net (code "159") (name "unconnected-(U6-PC7-Pad43)") (class "Default")
      (node (ref "U6") (pin "43") (pinfunction "PC7_43") (pintype "bidirectional"))
    )
    (net (code "160") (name "unconnected-(U6-PD0-Pad65)") (class "Default")
      (node (ref "U6") (pin "65") (pinfunction "PD0_65") (pintype "bidirectional"))
    )
    (net (code "161") (name "unconnected-(U6-PD2-Pad67)") (class "Default")
      (node (ref "U6") (pin "67") (pinfunction "PD2_67") (pintype "bidirectional"))
    )
    (net (code "162") (name "unconnected-(U6-PD3-Pad68)") (class "Default")
      (node (ref "U6") (pin "68") (pinfunction "PD3_68") (pintype "bidirectional"))
    )
    (net (code "163") (name "unconnected-(U6-PD4-DATA4-Pad83)") (class "Default")
      (node (ref "U6") (pin "83") (pinfunction "PD4-DATA4_83") (pintype "bidirectional"))
    )
    (net (code "164") (name "unconnected-(U6-PD5-DATA5-Pad84)") (class "Default")
      (node (ref "U6") (pin "84") (pinfunction "PD5-DATA5_84") (pintype "bidirectional"))
    )
    (net (code "165") (name "unconnected-(U6-PD6-DATA6-Pad85)") (class "Default")
      (node (ref "U6") (pin "85") (pinfunction "PD6-DATA6_85") (pintype "bidirectional"))
    )
    (net (code "166") (name "unconnected-(U6-PD7-DATA7-Pad86)") (class "Default")
      (node (ref "U6") (pin "86") (pinfunction "PD7-DATA7_86") (pintype "bidirectional"))
    )
    (net (code "167") (name "unconnected-(U6-PE0-XIRQ-Pad72)") (class "Default")
      (node (ref "U6") (pin "72") (pinfunction "PE0-XIRQ_72") (pintype "input"))
    )
    (net (code "168") (name "unconnected-(U6-PE1-IRQ-Pad71)") (class "Default")
      (node (ref "U6") (pin "71") (pinfunction "PE1-IRQ_71") (pintype "input"))
    )
    (net (code "169") (name "unconnected-(U6-PE2-Pad70)") (class "Default")
      (node (ref "U6") (pin "70") (pinfunction "PE2_70") (pintype "bidirectional"))
    )
    (net (code "170") (name "unconnected-(U6-PE3-Pad69)") (class "Default")
      (node (ref "U6") (pin "69") (pinfunction "PE3_69") (pintype "bidirectional"))
    )
    (net (code "171") (name "unconnected-(U6-PE4-Pad51)") (class "Default")
      (node (ref "U6") (pin "51") (pinfunction "PE4_51") (pintype "bidirectional"))
    )
    (net (code "172") (name "unconnected-(U6-PE5-Pad50)") (class "Default")
      (node (ref "U6") (pin "50") (pinfunction "PE5_50") (pintype "bidirectional"))
    )
    (net (code "173") (name "unconnected-(U6-PE6-Pad49)") (class "Default")
      (node (ref "U6") (pin "49") (pinfunction "PE6_49") (pintype "bidirectional"))
    )
    (net (code "174") (name "unconnected-(U6-PE7-Pad48)") (class "Default")
      (node (ref "U6") (pin "48") (pinfunction "PE7_48") (pintype "bidirectional"))
    )
    (net (code "175") (name "unconnected-(U6-PH4-Pad47)") (class "Default")
      (node (ref "U6") (pin "47") (pinfunction "PH4_47") (pintype "bidirectional"))
    )
    (net (code "176") (name "unconnected-(U6-PH5-Pad46)") (class "Default")
      (node (ref "U6") (pin "46") (pinfunction "PH5_46") (pintype "bidirectional"))
    )
    (net (code "177") (name "unconnected-(U6-PH6-Pad45)") (class "Default")
      (node (ref "U6") (pin "45") (pinfunction "PH6_45") (pintype "bidirectional"))
    )
    (net (code "178") (name "unconnected-(U6-PH7-Pad44)") (class "Default")
      (node (ref "U6") (pin "44") (pinfunction "PH7_44") (pintype "bidirectional"))
    )
    (net (code "179") (name "unconnected-(U6-PJ0-Pad24)") (class "Default")
      (node (ref "U6") (pin "24") (pinfunction "PJ0_24") (pintype "bidirectional"))
    )
    (net (code "180") (name "unconnected-(U6-PJ1-Pad23)") (class "Default")
      (node (ref "U6") (pin "23") (pinfunction "PJ1_23") (pintype "bidirectional"))
    )
    (net (code "181") (name "unconnected-(U6-PJ2-Pad5)") (class "Default")
      (node (ref "U6") (pin "5") (pinfunction "PJ2_5") (pintype "bidirectional"))
    )
    (net (code "182") (name "unconnected-(U6-PK3-Pad7)") (class "Default")
      (node (ref "U6") (pin "7") (pinfunction "PK3_7") (pintype "bidirectional"))
    )
    (net (code "183") (name "unconnected-(U6-PK4-Pad22)") (class "Default")
      (node (ref "U6") (pin "22") (pinfunction "PK4_22") (pintype "bidirectional"))
    )
    (net (code "184") (name "unconnected-(U6-PK5-Pad21)") (class "Default")
      (node (ref "U6") (pin "21") (pinfunction "PK5_21") (pintype "bidirectional"))
    )
    (net (code "185") (name "unconnected-(U6-PK6-Pad6)") (class "Default")
      (node (ref "U6") (pin "6") (pinfunction "PK6_6") (pintype "bidirectional"))
    )
    (net (code "186") (name "unconnected-(U6-PK7-Pad140)") (class "Default")
      (node (ref "U6") (pin "140") (pinfunction "PK7_140") (pintype "bidirectional"))
    )
    (net (code "187") (name "unconnected-(U6-PM0-Pad137)") (class "Default")
      (node (ref "U6") (pin "137") (pinfunction "PM0_137") (pintype "bidirectional"))
    )
    (net (code "188") (name "unconnected-(U6-PM1-Pad136)") (class "Default")
      (node (ref "U6") (pin "136") (pinfunction "PM1_136") (pintype "bidirectional"))
    )
    (net (code "189") (name "unconnected-(U6-PM4-Pad133)") (class "Default")
      (node (ref "U6") (pin "133") (pinfunction "PM4_133") (pintype "bidirectional"))
    )
    (net (code "190") (name "unconnected-(U6-PM5-Pad132)") (class "Default")
      (node (ref "U6") (pin "132") (pinfunction "PM5_132") (pintype "bidirectional"))
    )
    (net (code "191") (name "unconnected-(U6-PM6-Pad118)") (class "Default")
      (node (ref "U6") (pin "118") (pinfunction "PM6_118") (pintype "bidirectional"))
    )
    (net (code "192") (name "unconnected-(U6-PM7-Pad117)") (class "Default")
      (node (ref "U6") (pin "117") (pinfunction "PM7_117") (pintype "bidirectional"))
    )
    (net (code "193") (name "unconnected-(U6-PP0-Pad4)") (class "Default")
      (node (ref "U6") (pin "4") (pinfunction "PP0_4") (pintype "bidirectional"))
    )
    (net (code "194") (name "unconnected-(U6-PP1-Pad3)") (class "Default")
      (node (ref "U6") (pin "3") (pinfunction "PP1_3") (pintype "bidirectional"))
    )
    (net (code "195") (name "unconnected-(U6-PP2-Pad2)") (class "Default")
      (node (ref "U6") (pin "2") (pinfunction "PP2_2") (pintype "bidirectional"))
    )
    (net (code "196") (name "unconnected-(U6-PP3-Pad1)") (class "Default")
      (node (ref "U6") (pin "1") (pinfunction "PP3_1") (pintype "bidirectional"))
    )
    (net (code "197") (name "unconnected-(U6-PP4-Pad144)") (class "Default")
      (node (ref "U6") (pin "144") (pinfunction "PP4_144") (pintype "bidirectional"))
    )
    (net (code "198") (name "unconnected-(U6-PP5-Pad143)") (class "Default")
      (node (ref "U6") (pin "143") (pinfunction "PP5_143") (pintype "bidirectional"))
    )
    (net (code "199") (name "unconnected-(U6-PP6-Pad142)") (class "Default")
      (node (ref "U6") (pin "142") (pinfunction "PP6_142") (pintype "bidirectional"))
    )
    (net (code "200") (name "unconnected-(U6-PP7-Pad141)") (class "Default")
      (node (ref "U6") (pin "141") (pinfunction "PP7_141") (pintype "bidirectional"))
    )
    (net (code "201") (name "unconnected-(U6-PS4-Pad123)") (class "Default")
      (node (ref "U6") (pin "123") (pinfunction "PS4_123") (pintype "bidirectional"))
    )
    (net (code "202") (name "unconnected-(U6-PS5-Pad124)") (class "Default")
      (node (ref "U6") (pin "124") (pinfunction "PS5_124") (pintype "bidirectional"))
    )
    (net (code "203") (name "unconnected-(U6-PS6-Pad125)") (class "Default")
      (node (ref "U6") (pin "125") (pinfunction "PS6_125") (pintype "bidirectional"))
    )
    (net (code "204") (name "unconnected-(U6-PS7-Pad126)") (class "Default")
      (node (ref "U6") (pin "126") (pinfunction "PS7_126") (pintype "bidirectional"))
    )
    (net (code "205") (name "unconnected-(U6-PT0-Pad11)") (class "Default")
      (node (ref "U6") (pin "11") (pinfunction "PT0_11") (pintype "bidirectional"))
    )
    (net (code "206") (name "unconnected-(U6-PT1-Pad12)") (class "Default")
      (node (ref "U6") (pin "12") (pinfunction "PT1_12") (pintype "bidirectional"))
    )
    (net (code "207") (name "unconnected-(U6-PT2-Pad13)") (class "Default")
      (node (ref "U6") (pin "13") (pinfunction "PT2_13") (pintype "bidirectional"))
    )
    (net (code "208") (name "unconnected-(U6-PT3-Pad14)") (class "Default")
      (node (ref "U6") (pin "14") (pinfunction "PT3_14") (pintype "bidirectional"))
    )
    (net (code "209") (name "unconnected-(U6-PT4-Pad17)") (class "Default")
      (node (ref "U6") (pin "17") (pinfunction "PT4_17") (pintype "bidirectional"))
    )
    (net (code "210") (name "unconnected-(U6-PT5-Pad18)") (class "Default")
      (node (ref "U6") (pin "18") (pinfunction "PT5_18") (pintype "bidirectional"))
    )
    (net (code "211") (name "unconnected-(U6-PT6-Pad19)") (class "Default")
      (node (ref "U6") (pin "19") (pinfunction "PT6_19") (pintype "bidirectional"))
    )
    (net (code "212") (name "unconnected-(U6-PT7-Pad20)") (class "Default")
      (node (ref "U6") (pin "20") (pinfunction "PT7_20") (pintype "bidirectional"))
    )
    (net (code "213") (name "unconnected-(X1-Pad2)") (class "Default")
      (node (ref "X1") (pin "2") (pinfunction "2_2") (pintype "bidirectional"))
    )
    (net (code "214") (name "unconnected-(X1-Pad3)") (class "Default")
      (node (ref "X1") (pin "3") (pinfunction "3_3") (pintype "bidirectional"))
    )
    (net (code "215") (name "unconnected-(X1-Pad18)") (class "Default")
      (node (ref "X1") (pin "18") (pinfunction "18_18") (pintype "bidirectional"))
    )
    (net (code "216") (name "unconnected-(X1-Pad19)") (class "Default")
      (node (ref "X1") (pin "19") (pinfunction "19_19") (pintype "bidirectional"))
    )
    (net (code "217") (name "unconnected-(X2-Pad1)") (class "Default")
      (node (ref "X2") (pin "1") (pinfunction "1_1") (pintype "bidirectional"))
    )
    (net (code "218") (name "unconnected-(X2-Pad2)") (class "Default")
      (node (ref "X2") (pin "2") (pinfunction "2_2") (pintype "bidirectional"))
    )
    (net (code "219") (name "unconnected-(X2-Pad3)") (class "Default")
      (node (ref "X2") (pin "3") (pinfunction "3_3") (pintype "bidirectional"))
    )
    (net (code "220") (name "unconnected-(X2-Pad16)") (class "Default")
      (node (ref "X2") (pin "16") (pinfunction "16_16") (pintype "bidirectional"))
    )
    (net (code "221") (name "unconnected-(X2-Pad17)") (class "Default")
      (node (ref "X2") (pin "17") (pinfunction "17_17") (pintype "bidirectional"))
    )
    (net (code "222") (name "unconnected-(X5-NC-Pad3)") (class "Default")
      (node (ref "X5") (pin "3") (pinfunction "NC_3") (pintype "bidirectional"))
    )
    (net (code "223") (name "unconnected-(X5-VPP-Pad5)") (class "Default")
      (node (ref "X5") (pin "5") (pinfunction "VPP_5") (pintype "bidirectional"))
    )
  )
)
